# Schematic.net
KiCad netlist of a schematic drawn in Altium Designer
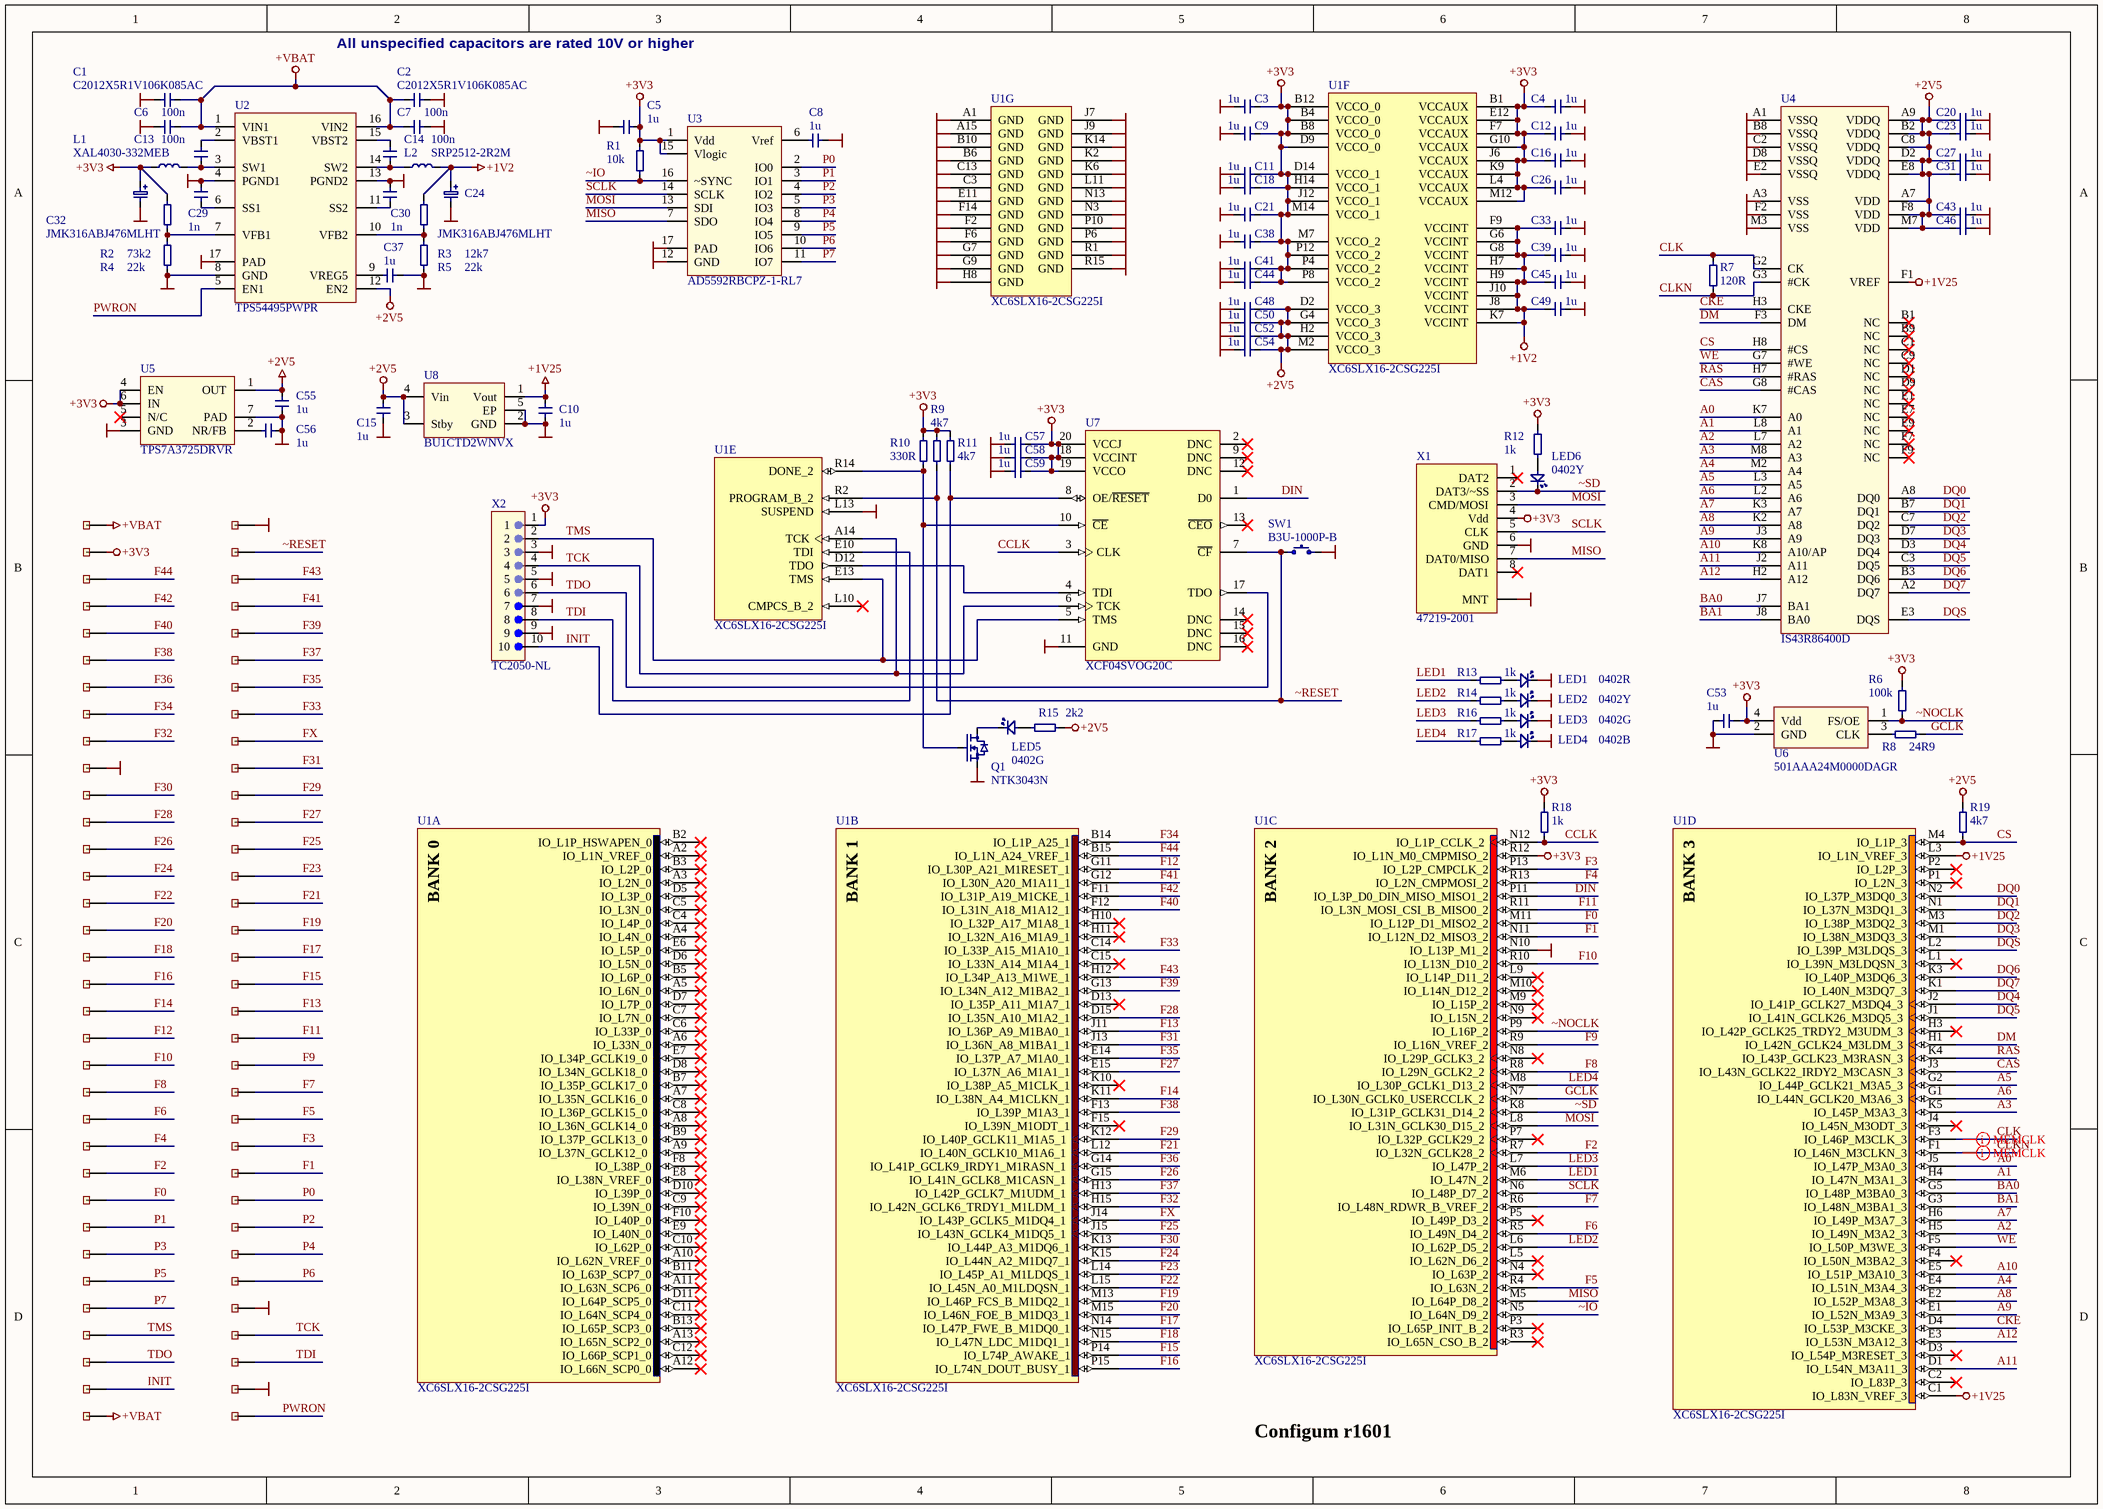
[diagram p0: Schematic.SchDoc]

(export (version "E")
  (design (tool "Eeschema 10.0.6"))
  (components
    (comp (ref "C1")
      (value "C2012X5R1V106K085AC")
      (footprint "_0805")
      (description "Capacitor")
      (libsource (lib "Discretes") (part "Capacitor"))
    )
    (comp (ref "C2")
      (value "C2012X5R1V106K085AC")
      (footprint "_0805")
      (description "Capacitor")
      (libsource (lib "Discretes") (part "Capacitor"))
    )
    (comp (ref "C3")
      (value "1u")
      (footprint "_0402")
      (description "Capacitor")
      (libsource (lib "Discretes") (part "Capacitor"))
    )
    (comp (ref "C4")
      (value "1u")
      (footprint "_0402")
      (description "Capacitor")
      (libsource (lib "Discretes") (part "Capacitor"))
    )
    (comp (ref "C5")
      (value "1u")
      (footprint "_0402")
      (description "Capacitor")
      (libsource (lib "Discretes") (part "Capacitor"))
    )
    (comp (ref "C6")
      (value "100n")
      (footprint "_0402")
      (description "Capacitor")
      (libsource (lib "Discretes") (part "Capacitor"))
    )
    (comp (ref "C7")
      (value "100n")
      (footprint "_0402")
      (description "Capacitor")
      (libsource (lib "Discretes") (part "Capacitor"))
    )
    (comp (ref "C8")
      (value "1u")
      (footprint "_0402")
      (description "Capacitor")
      (libsource (lib "Discretes") (part "Capacitor"))
    )
    (comp (ref "C9")
      (value "1u")
      (footprint "_0402")
      (description "Capacitor")
      (libsource (lib "Discretes") (part "Capacitor"))
    )
    (comp (ref "C10")
      (value "1u")
      (footprint "_0402")
      (description "Capacitor")
      (libsource (lib "Discretes") (part "Capacitor"))
    )
    (comp (ref "C11")
      (value "1u")
      (footprint "_0402")
      (description "Capacitor")
      (libsource (lib "Discretes") (part "Capacitor"))
    )
    (comp (ref "C12")
      (value "1u")
      (footprint "_0402")
      (description "Capacitor")
      (libsource (lib "Discretes") (part "Capacitor"))
    )
    (comp (ref "C13")
      (value "100n")
      (footprint "_0402")
      (description "Capacitor")
      (libsource (lib "Discretes") (part "Capacitor"))
    )
    (comp (ref "C14")
      (value "100n")
      (footprint "_0402")
      (description "Capacitor")
      (libsource (lib "Discretes") (part "Capacitor"))
    )
    (comp (ref "C15")
      (value "1u")
      (footprint "_0402")
      (description "Capacitor")
      (libsource (lib "Discretes") (part "Capacitor"))
    )
    (comp (ref "C16")
      (value "1u")
      (footprint "_0402")
      (description "Capacitor")
      (libsource (lib "Discretes") (part "Capacitor"))
    )
    (comp (ref "C18")
      (value "1u")
      (footprint "_0402")
      (description "Capacitor")
      (libsource (lib "Discretes") (part "Capacitor"))
    )
    (comp (ref "C20")
      (value "1u")
      (footprint "_0402")
      (description "Capacitor")
      (libsource (lib "Discretes") (part "Capacitor"))
    )
    (comp (ref "C21")
      (value "1u")
      (footprint "_0402")
      (description "Capacitor")
      (libsource (lib "Discretes") (part "Capacitor"))
    )
    (comp (ref "C23")
      (value "1u")
      (footprint "_0402")
      (description "Capacitor")
      (libsource (lib "Discretes") (part "Capacitor"))
    )
    (comp (ref "C24")
      (value "JMK316ABJ476MLHT")
      (footprint "Case A (3216)")
      (description "Polar capacitor")
      (libsource (lib "Discretes") (part "Capacitor+"))
    )
    (comp (ref "C26")
      (value "1u")
      (footprint "_0402")
      (description "Capacitor")
      (libsource (lib "Discretes") (part "Capacitor"))
    )
    (comp (ref "C27")
      (value "1u")
      (footprint "_0402")
      (description "Capacitor")
      (libsource (lib "Discretes") (part "Capacitor"))
    )
    (comp (ref "C29")
      (value "1n")
      (footprint "_0402")
      (description "Capacitor")
      (libsource (lib "Discretes") (part "Capacitor"))
    )
    (comp (ref "C30")
      (value "1n")
      (footprint "_0402")
      (description "Capacitor")
      (libsource (lib "Discretes") (part "Capacitor"))
    )
    (comp (ref "C31")
      (value "1u")
      (footprint "_0402")
      (description "Capacitor")
      (libsource (lib "Discretes") (part "Capacitor"))
    )
    (comp (ref "C32")
      (value "JMK316ABJ476MLHT")
      (footprint "Case A (3216)")
      (description "Polar capacitor")
      (libsource (lib "Discretes") (part "Capacitor+"))
    )
    (comp (ref "C33")
      (value "1u")
      (footprint "_0402")
      (description "Capacitor")
      (libsource (lib "Discretes") (part "Capacitor"))
    )
    (comp (ref "C37")
      (value "1u")
      (footprint "_0402")
      (description "Capacitor")
      (libsource (lib "Discretes") (part "Capacitor"))
    )
    (comp (ref "C38")
      (value "1u")
      (footprint "_0402")
      (description "Capacitor")
      (libsource (lib "Discretes") (part "Capacitor"))
    )
    (comp (ref "C39")
      (value "1u")
      (footprint "_0402")
      (description "Capacitor")
      (libsource (lib "Discretes") (part "Capacitor"))
    )
    (comp (ref "C41")
      (value "1u")
      (footprint "_0402")
      (description "Capacitor")
      (libsource (lib "Discretes") (part "Capacitor"))
    )
    (comp (ref "C43")
      (value "1u")
      (footprint "_0402")
      (description "Capacitor")
      (libsource (lib "Discretes") (part "Capacitor"))
    )
    (comp (ref "C44")
      (value "1u")
      (footprint "_0402")
      (description "Capacitor")
      (libsource (lib "Discretes") (part "Capacitor"))
    )
    (comp (ref "C45")
      (value "1u")
      (footprint "_0402")
      (description "Capacitor")
      (libsource (lib "Discretes") (part "Capacitor"))
    )
    (comp (ref "C46")
      (value "1u")
      (footprint "_0402")
      (description "Capacitor")
      (libsource (lib "Discretes") (part "Capacitor"))
    )
    (comp (ref "C48")
      (value "1u")
      (footprint "_0402")
      (description "Capacitor")
      (libsource (lib "Discretes") (part "Capacitor"))
    )
    (comp (ref "C49")
      (value "1u")
      (footprint "_0402")
      (description "Capacitor")
      (libsource (lib "Discretes") (part "Capacitor"))
    )
    (comp (ref "C50")
      (value "1u")
      (footprint "_0402")
      (description "Capacitor")
      (libsource (lib "Discretes") (part "Capacitor"))
    )
    (comp (ref "C52")
      (value "1u")
      (footprint "_0402")
      (description "Capacitor")
      (libsource (lib "Discretes") (part "Capacitor"))
    )
    (comp (ref "C53")
      (value "1u")
      (footprint "_0402")
      (description "Capacitor")
      (libsource (lib "Discretes") (part "Capacitor"))
    )
    (comp (ref "C54")
      (value "1u")
      (footprint "_0402")
      (description "Capacitor")
      (libsource (lib "Discretes") (part "Capacitor"))
    )
    (comp (ref "C55")
      (value "1u")
      (footprint "_0402")
      (description "Capacitor")
      (libsource (lib "Discretes") (part "Capacitor"))
    )
    (comp (ref "C56")
      (value "1u")
      (footprint "_0402")
      (description "Capacitor")
      (libsource (lib "Discretes") (part "Capacitor"))
    )
    (comp (ref "C57")
      (value "1u")
      (footprint "_0402")
      (description "Capacitor")
      (libsource (lib "Discretes") (part "Capacitor"))
    )
    (comp (ref "C58")
      (value "1u")
      (footprint "_0402")
      (description "Capacitor")
      (libsource (lib "Discretes") (part "Capacitor"))
    )
    (comp (ref "C59")
      (value "1u")
      (footprint "_0402")
      (description "Capacitor")
      (libsource (lib "Discretes") (part "Capacitor"))
    )
    (comp (ref "L1")
      (value "XAL4030-332MEB")
      (footprint "IND_4X4")
      (description "Inductor")
      (libsource (lib "Discretes") (part "Inductor"))
    )
    (comp (ref "L2")
      (value "SRP2512-2R2M")
      (footprint "IND_2.5x2")
      (description "Inductor")
      (libsource (lib "") (part "Inductor_1"))
    )
    (comp (ref "LED1")
      (value "0402R")
      (footprint "_0402+")
      (description "Light Emitting Diode")
      (libsource (lib "") (part "LED_1"))
    )
    (comp (ref "LED2")
      (value "0402Y")
      (footprint "_0402+")
      (description "Light Emitting Diode")
      (libsource (lib "") (part "LED_1"))
    )
    (comp (ref "LED3")
      (value "0402G")
      (footprint "_0402+")
      (description "Light Emitting Diode")
      (libsource (lib "") (part "LED_1"))
    )
    (comp (ref "LED4")
      (value "0402B")
      (footprint "_0402+")
      (description "Light Emitting Diode")
      (libsource (lib "") (part "LED_1"))
    )
    (comp (ref "LED5")
      (value "0402G")
      (footprint "_0402+")
      (description "Light Emitting Diode")
      (libsource (lib "Discretes") (part "LED"))
    )
    (comp (ref "LED6")
      (value "0402Y")
      (footprint "_0402+")
      (description "Light Emitting Diode")
      (libsource (lib "Discretes") (part "LED"))
    )
    (comp (ref "PIN1")
      (value "Pin/Pad")
      (footprint "PLCC68 pin")
      (description "Single pin/pad")
      (libsource (lib "") (part "Pin/Pad_56"))
    )
    (comp (ref "PIN2")
      (value "Pin/Pad")
      (footprint "PLCC68 pin")
      (description "Single pin/pad")
      (libsource (lib "") (part "Pin/Pad_62"))
    )
    (comp (ref "PIN3")
      (value "Pin/Pad")
      (footprint "PLCC68 pin")
      (description "Single pin/pad")
      (libsource (lib "") (part "Pin/Pad_10"))
    )
    (comp (ref "PIN4")
      (value "Pin/Pad")
      (footprint "PLCC68 pin")
      (description "Single pin/pad")
      (libsource (lib "") (part "Pin/Pad_3"))
    )
    (comp (ref "PIN5")
      (value "Pin/Pad")
      (footprint "PLCC68 pin")
      (description "Single pin/pad")
      (libsource (lib "") (part "Pin/Pad_43"))
    )
    (comp (ref "PIN6")
      (value "Pin/Pad")
      (footprint "PLCC68 pin")
      (description "Single pin/pad")
      (libsource (lib "") (part "Pin/Pad_8"))
    )
    (comp (ref "PIN7")
      (value "Pin/Pad")
      (footprint "PLCC68 pin")
      (description "Single pin/pad")
      (libsource (lib "Connectors") (part "Pin/Pad"))
    )
    (comp (ref "PIN8")
      (value "Pin/Pad")
      (footprint "PLCC68 pin")
      (description "Single pin/pad")
      (libsource (lib "") (part "Pin/Pad_17"))
    )
    (comp (ref "PIN9")
      (value "Pin/Pad")
      (footprint "PLCC68 pin")
      (description "Single pin/pad")
      (libsource (lib "") (part "Pin/Pad_23"))
    )
    (comp (ref "PIN10")
      (value "Pin/Pad")
      (footprint "PLCC68 pin")
      (description "Single pin/pad")
      (libsource (lib "") (part "Pin/Pad_14"))
    )
    (comp (ref "PIN11")
      (value "Pin/Pad")
      (footprint "PLCC68 pin")
      (description "Single pin/pad")
      (libsource (lib "") (part "Pin/Pad_6"))
    )
    (comp (ref "PIN12")
      (value "Pin/Pad")
      (footprint "PLCC68 pin")
      (description "Single pin/pad")
      (libsource (lib "") (part "Pin/Pad_39"))
    )
    (comp (ref "PIN13")
      (value "Pin/Pad")
      (footprint "PLCC68 pin")
      (description "Single pin/pad")
      (libsource (lib "") (part "Pin/Pad_1"))
    )
    (comp (ref "PIN14")
      (value "Pin/Pad")
      (footprint "PLCC68 pin")
      (description "Single pin/pad")
      (libsource (lib "") (part "Pin/Pad_25"))
    )
    (comp (ref "PIN15")
      (value "Pin/Pad")
      (footprint "PLCC68 pin")
      (description "Single pin/pad")
      (libsource (lib "") (part "Pin/Pad_61"))
    )
    (comp (ref "PIN16")
      (value "Pin/Pad")
      (footprint "PLCC68 pin")
      (description "Single pin/pad")
      (libsource (lib "") (part "Pin/Pad_4"))
    )
    (comp (ref "PIN17")
      (value "Pin/Pad")
      (footprint "PLCC68 pin")
      (description "Single pin/pad")
      (libsource (lib "") (part "Pin/Pad_11"))
    )
    (comp (ref "PIN18")
      (value "Pin/Pad")
      (footprint "PLCC68 pin")
      (description "Single pin/pad")
      (libsource (lib "") (part "Pin/Pad_67"))
    )
    (comp (ref "PIN19")
      (value "Pin/Pad")
      (footprint "PLCC68 pin")
      (description "Single pin/pad")
      (libsource (lib "") (part "Pin/Pad_28"))
    )
    (comp (ref "PIN20")
      (value "Pin/Pad")
      (footprint "PLCC68 pin")
      (description "Single pin/pad")
      (libsource (lib "") (part "Pin/Pad_59"))
    )
    (comp (ref "PIN21")
      (value "Pin/Pad")
      (footprint "PLCC68 pin")
      (description "Single pin/pad")
      (libsource (lib "") (part "Pin/Pad_55"))
    )
    (comp (ref "PIN22")
      (value "Pin/Pad")
      (footprint "PLCC68 pin")
      (description "Single pin/pad")
      (libsource (lib "") (part "Pin/Pad_5"))
    )
    (comp (ref "PIN23")
      (value "Pin/Pad")
      (footprint "PLCC68 pin")
      (description "Single pin/pad")
      (libsource (lib "") (part "Pin/Pad_53"))
    )
    (comp (ref "PIN24")
      (value "Pin/Pad")
      (footprint "PLCC68 pin")
      (description "Single pin/pad")
      (libsource (lib "") (part "Pin/Pad_13"))
    )
    (comp (ref "PIN25")
      (value "Pin/Pad")
      (footprint "PLCC68 pin")
      (description "Single pin/pad")
      (libsource (lib "") (part "Pin/Pad_42"))
    )
    (comp (ref "PIN26")
      (value "Pin/Pad")
      (footprint "PLCC68 pin")
      (description "Single pin/pad")
      (libsource (lib "") (part "Pin/Pad_15"))
    )
    (comp (ref "PIN27")
      (value "Pin/Pad")
      (footprint "PLCC68 pin")
      (description "Single pin/pad")
      (libsource (lib "") (part "Pin/Pad_54"))
    )
    (comp (ref "PIN28")
      (value "Pin/Pad")
      (footprint "PLCC68 pin")
      (description "Single pin/pad")
      (libsource (lib "") (part "Pin/Pad_2"))
    )
    (comp (ref "PIN29")
      (value "Pin/Pad")
      (footprint "PLCC68 pin")
      (description "Single pin/pad")
      (libsource (lib "") (part "Pin/Pad_63"))
    )
    (comp (ref "PIN30")
      (value "Pin/Pad")
      (footprint "PLCC68 pin")
      (description "Single pin/pad")
      (libsource (lib "") (part "Pin/Pad_36"))
    )
    (comp (ref "PIN31")
      (value "Pin/Pad")
      (footprint "PLCC68 pin")
      (description "Single pin/pad")
      (libsource (lib "") (part "Pin/Pad_45"))
    )
    (comp (ref "PIN32")
      (value "Pin/Pad")
      (footprint "PLCC68 pin")
      (description "Single pin/pad")
      (libsource (lib "") (part "Pin/Pad_46"))
    )
    (comp (ref "PIN33")
      (value "Pin/Pad")
      (footprint "PLCC68 pin")
      (description "Single pin/pad")
      (libsource (lib "") (part "Pin/Pad_18"))
    )
    (comp (ref "PIN34")
      (value "Pin/Pad")
      (footprint "PLCC68 pin")
      (description "Single pin/pad")
      (libsource (lib "") (part "Pin/Pad_50"))
    )
    (comp (ref "PIN35")
      (value "Pin/Pad")
      (footprint "PLCC68 pin")
      (description "Single pin/pad")
      (libsource (lib "") (part "Pin/Pad_65"))
    )
    (comp (ref "PIN36")
      (value "Pin/Pad")
      (footprint "PLCC68 pin")
      (description "Single pin/pad")
      (libsource (lib "") (part "Pin/Pad_35"))
    )
    (comp (ref "PIN37")
      (value "Pin/Pad")
      (footprint "PLCC68 pin")
      (description "Single pin/pad")
      (libsource (lib "") (part "Pin/Pad_31"))
    )
    (comp (ref "PIN38")
      (value "Pin/Pad")
      (footprint "PLCC68 pin")
      (description "Single pin/pad")
      (libsource (lib "") (part "Pin/Pad_66"))
    )
    (comp (ref "PIN39")
      (value "Pin/Pad")
      (footprint "PLCC68 pin")
      (description "Single pin/pad")
      (libsource (lib "") (part "Pin/Pad_9"))
    )
    (comp (ref "PIN40")
      (value "Pin/Pad")
      (footprint "PLCC68 pin")
      (description "Single pin/pad")
      (libsource (lib "") (part "Pin/Pad_58"))
    )
    (comp (ref "PIN41")
      (value "Pin/Pad")
      (footprint "PLCC68 pin")
      (description "Single pin/pad")
      (libsource (lib "") (part "Pin/Pad_26"))
    )
    (comp (ref "PIN42")
      (value "Pin/Pad")
      (footprint "PLCC68 pin")
      (description "Single pin/pad")
      (libsource (lib "") (part "Pin/Pad_12"))
    )
    (comp (ref "PIN43")
      (value "Pin/Pad")
      (footprint "PLCC68 pin")
      (description "Single pin/pad")
      (libsource (lib "") (part "Pin/Pad_49"))
    )
    (comp (ref "PIN44")
      (value "Pin/Pad")
      (footprint "PLCC68 pin")
      (description "Single pin/pad")
      (libsource (lib "") (part "Pin/Pad_21"))
    )
    (comp (ref "PIN45")
      (value "Pin/Pad")
      (footprint "PLCC68 pin")
      (description "Single pin/pad")
      (libsource (lib "") (part "Pin/Pad_33"))
    )
    (comp (ref "PIN46")
      (value "Pin/Pad")
      (footprint "PLCC68 pin")
      (description "Single pin/pad")
      (libsource (lib "") (part "Pin/Pad_20"))
    )
    (comp (ref "PIN47")
      (value "Pin/Pad")
      (footprint "PLCC68 pin")
      (description "Single pin/pad")
      (libsource (lib "") (part "Pin/Pad_16"))
    )
    (comp (ref "PIN48")
      (value "Pin/Pad")
      (footprint "PLCC68 pin")
      (description "Single pin/pad")
      (libsource (lib "") (part "Pin/Pad_22"))
    )
    (comp (ref "PIN49")
      (value "Pin/Pad")
      (footprint "PLCC68 pin")
      (description "Single pin/pad")
      (libsource (lib "") (part "Pin/Pad_32"))
    )
    (comp (ref "PIN50")
      (value "Pin/Pad")
      (footprint "PLCC68 pin")
      (description "Single pin/pad")
      (libsource (lib "") (part "Pin/Pad_41"))
    )
    (comp (ref "PIN51")
      (value "Pin/Pad")
      (footprint "PLCC68 pin")
      (description "Single pin/pad")
      (libsource (lib "") (part "Pin/Pad_37"))
    )
    (comp (ref "PIN52")
      (value "Pin/Pad")
      (footprint "PLCC68 pin")
      (description "Single pin/pad")
      (libsource (lib "") (part "Pin/Pad_47"))
    )
    (comp (ref "PIN53")
      (value "Pin/Pad")
      (footprint "PLCC68 pin")
      (description "Single pin/pad")
      (libsource (lib "") (part "Pin/Pad_19"))
    )
    (comp (ref "PIN54")
      (value "Pin/Pad")
      (footprint "PLCC68 pin")
      (description "Single pin/pad")
      (libsource (lib "") (part "Pin/Pad_60"))
    )
    (comp (ref "PIN55")
      (value "Pin/Pad")
      (footprint "PLCC68 pin")
      (description "Single pin/pad")
      (libsource (lib "") (part "Pin/Pad_51"))
    )
    (comp (ref "PIN56")
      (value "Pin/Pad")
      (footprint "PLCC68 pin")
      (description "Single pin/pad")
      (libsource (lib "") (part "Pin/Pad_29"))
    )
    (comp (ref "PIN57")
      (value "Pin/Pad")
      (footprint "PLCC68 pin")
      (description "Single pin/pad")
      (libsource (lib "") (part "Pin/Pad_57"))
    )
    (comp (ref "PIN58")
      (value "Pin/Pad")
      (footprint "PLCC68 pin")
      (description "Single pin/pad")
      (libsource (lib "") (part "Pin/Pad_48"))
    )
    (comp (ref "PIN59")
      (value "Pin/Pad")
      (footprint "PLCC68 pin")
      (description "Single pin/pad")
      (libsource (lib "") (part "Pin/Pad_38"))
    )
    (comp (ref "PIN60")
      (value "Pin/Pad")
      (footprint "PLCC68 pin")
      (description "Single pin/pad")
      (libsource (lib "") (part "Pin/Pad_24"))
    )
    (comp (ref "PIN61")
      (value "Pin/Pad")
      (footprint "PLCC68 pin")
      (description "Single pin/pad")
      (libsource (lib "") (part "Pin/Pad_44"))
    )
    (comp (ref "PIN62")
      (value "Pin/Pad")
      (footprint "PLCC68 pin")
      (description "Single pin/pad")
      (libsource (lib "") (part "Pin/Pad_52"))
    )
    (comp (ref "PIN63")
      (value "Pin/Pad")
      (footprint "PLCC68 pin")
      (description "Single pin/pad")
      (libsource (lib "") (part "Pin/Pad_40"))
    )
    (comp (ref "PIN64")
      (value "Pin/Pad")
      (footprint "PLCC68 pin")
      (description "Single pin/pad")
      (libsource (lib "") (part "Pin/Pad_7"))
    )
    (comp (ref "PIN65")
      (value "Pin/Pad")
      (footprint "PLCC68 pin")
      (description "Single pin/pad")
      (libsource (lib "") (part "Pin/Pad_34"))
    )
    (comp (ref "PIN66")
      (value "Pin/Pad")
      (footprint "PLCC68 pin")
      (description "Single pin/pad")
      (libsource (lib "") (part "Pin/Pad_64"))
    )
    (comp (ref "PIN67")
      (value "Pin/Pad")
      (footprint "PLCC68 pin")
      (description "Single pin/pad")
      (libsource (lib "") (part "Pin/Pad_30"))
    )
    (comp (ref "PIN68")
      (value "Pin/Pad")
      (footprint "PLCC68 pin")
      (description "Single pin/pad")
      (libsource (lib "") (part "Pin/Pad_27"))
    )
    (comp (ref "Q1")
      (value "NTK3043N")
      (footprint "SC105-3")
      (description "N-channel FET transistor")
      (libsource (lib "Discretes") (part "N-FET"))
    )
    (comp (ref "R1")
      (value "10k")
      (footprint "_0402")
      (description "Resistor")
      (libsource (lib "") (part "Resistor_2"))
    )
    (comp (ref "R2")
      (value "73k2")
      (footprint "_0402")
      (description "Resistor")
      (libsource (lib "Discretes") (part "Resistor"))
    )
    (comp (ref "R3")
      (value "12k7")
      (footprint "_0402")
      (description "Resistor")
      (libsource (lib "Discretes") (part "Resistor"))
    )
    (comp (ref "R4")
      (value "22k")
      (footprint "_0402")
      (description "Resistor")
      (libsource (lib "Discretes") (part "Resistor"))
    )
    (comp (ref "R5")
      (value "22k")
      (footprint "_0402")
      (description "Resistor")
      (libsource (lib "Discretes") (part "Resistor"))
    )
    (comp (ref "R6")
      (value "100k")
      (footprint "_0402")
      (description "Resistor")
      (libsource (lib "") (part "Resistor_2"))
    )
    (comp (ref "R7")
      (value "120R")
      (footprint "_0402")
      (description "Resistor")
      (libsource (lib "") (part "Resistor_2"))
    )
    (comp (ref "R8")
      (value "24R9")
      (footprint "_0402")
      (description "Resistor")
      (libsource (lib "") (part "Resistor_3"))
    )
    (comp (ref "R9")
      (value "4k7")
      (footprint "_0402")
      (description "Resistor")
      (libsource (lib "") (part "Resistor_2"))
    )
    (comp (ref "R10")
      (value "330R")
      (footprint "_0402")
      (description "Resistor")
      (libsource (lib "") (part "Resistor_2"))
    )
    (comp (ref "R11")
      (value "4k7")
      (footprint "_0402")
      (description "Resistor")
      (libsource (lib "") (part "Resistor_2"))
    )
    (comp (ref "R12")
      (value "1k")
      (footprint "_0402")
      (description "Resistor")
      (libsource (lib "") (part "Resistor_2"))
    )
    (comp (ref "R13")
      (value "1k")
      (footprint "_0402")
      (description "Resistor")
      (libsource (lib "") (part "Resistor_1"))
    )
    (comp (ref "R14")
      (value "1k")
      (footprint "_0402")
      (description "Resistor")
      (libsource (lib "") (part "Resistor_1"))
    )
    (comp (ref "R15")
      (value "2k2")
      (footprint "_0402")
      (description "Resistor")
      (libsource (lib "") (part "Resistor_3"))
    )
    (comp (ref "R16")
      (value "1k")
      (footprint "_0402")
      (description "Resistor")
      (libsource (lib "") (part "Resistor_1"))
    )
    (comp (ref "R17")
      (value "1k")
      (footprint "_0402")
      (description "Resistor")
      (libsource (lib "") (part "Resistor_1"))
    )
    (comp (ref "R18")
      (value "1k")
      (footprint "_0402")
      (description "Resistor")
      (libsource (lib "Discretes") (part "Resistor"))
    )
    (comp (ref "R19")
      (value "4k7")
      (footprint "_0402")
      (description "Resistor")
      (libsource (lib "Discretes") (part "Resistor"))
    )
    (comp (ref "SW1")
      (value "B3U-1000P-B")
      (footprint "B3U-1000P-B")
      (description "Switch, Momentary, Normal Open, SPST")
      (libsource (lib "Switches") (part "Switch MNO SPST"))
    )
    (comp (ref "U1")
      (value "XC6SLX16-2CSG225I")
      (footprint "CSG225")
      (libsource (lib "Xilinx Spartan-6") (part "XC6SLX16-2CSG225I"))
    )
    (comp (ref "U2")
      (value "TPS54495PWPR")
      (footprint "TSOP65P650X110_HS-16N")
      (description "4A/2A Dual Channel Synchronous Step-Down Switcher with Integrated FET")
      (fields (field (name "MANUFACTURER") "Texas Instruments"))
      (libsource (lib "IC Power Supply") (part "TPS54495 TSSOP16"))
    )
    (comp (ref "U3")
      (value "AD5592RBCPZ-1-RL7")
      (footprint "QFN50P300X300-16V4N")
      (description "8-Channel, 12-Bit, Configurable ADC/DAC with On-Chip Reference, SPI Interface")
      (fields (field (name "MANUFACTURER") "Analog Devices"))
      (libsource (lib "IC Other Functions") (part "AD5592R-1 QFN16"))
    )
    (comp (ref "U4")
      (value "IS43R86400D")
      (footprint "BGA60C80P12X9_1300X800X120")
      (description "64Mx8 DDR SDRAM")
      (fields (field (name "MANUFACTURER") "ISSI"))
      (libsource (lib "IC Other Functions") (part "IS43R86400D FBGA60"))
    )
    (comp (ref "U5")
      (value "TPS7A3725DRVR")
      (footprint "SON65P200x200_HS-6N")
      (description "1% High-Accuracy, 1-A, Low-Dropout Regulator  with Reverse Current Protection")
      (fields (field (name "MANUFACTURER") "Texas Instruments"))
      (libsource (lib "IC Power Supply") (part "TPS7A37"))
    )
    (comp (ref "U6")
      (value "501AAA24M0000DAGR")
      (footprint "Osc 25x20 (4)")
      (description "32kHz –100MHz CMEMS Oscillator")
      (fields (field (name "MANUFACTURER") "Silicon Labs"))
      (libsource (lib "IC Other Functions") (part "Si50x"))
    )
    (comp (ref "U7")
      (value "XCF04SVOG20C")
      (footprint "VOG20_L")
      (libsource (lib "Xilinx XCF") (part "XCF04SVOG20C"))
    )
    (comp (ref "U8")
      (value "BU1CTD2WNVX")
      (footprint "DFN65P100x100-4")
      (description "1.25V 200mA LDO in 1mm x 1mm package")
      (fields (field (name "MANUFACTURER") "Rohm"))
      (libsource (lib "IC Power Supply") (part "BUxxTD2WNVX"))
    )
    (comp (ref "X1")
      (value "47219-2001")
      (footprint "MOLEX_47219-2001")
      (description "microSD card connector")
      (libsource (lib "Connectors") (part "microSD"))
    )
    (comp (ref "X2")
      (value "TC2050-NL")
      (footprint "TC2050-NL")
      (description "TC2050 nails connector")
      (fields (field (name "MANUFACTURER") "www.tag-connect.com"))
      (libsource (lib "Connectors") (part "TC2050"))
    )
  )
  (nets
    (net (code "1") (name "+1V2") (class "Default")
      (node (ref "C24") (pin "1") (pintype "passive"))
      (node (ref "C33") (pin "1") (pintype "passive"))
      (node (ref "C39") (pin "1") (pintype "passive"))
      (node (ref "C45") (pin "1") (pintype "passive"))
      (node (ref "C49") (pin "1") (pintype "passive"))
      (node (ref "L2") (pin "1") (pintype "passive"))
      (node (ref "R3") (pin "2") (pintype "passive"))
      (node (ref "U1") (pin "F9") (pinfunction "VCCINT_F9") (pintype "power_in"))
      (node (ref "U1") (pin "G6") (pinfunction "VCCINT_G6") (pintype "power_in"))
      (node (ref "U1") (pin "G8") (pinfunction "VCCINT_G8") (pintype "power_in"))
      (node (ref "U1") (pin "H7") (pinfunction "VCCINT_H7") (pintype "power_in"))
      (node (ref "U1") (pin "H9") (pinfunction "VCCINT_H9") (pintype "power_in"))
      (node (ref "U1") (pin "J10") (pinfunction "VCCINT_J10") (pintype "power_in"))
      (node (ref "U1") (pin "J8") (pinfunction "VCCINT_J8") (pintype "power_in"))
      (node (ref "U1") (pin "K7") (pinfunction "VCCINT_K7") (pintype "power_in"))
    )
    (net (code "2") (name "+1V25") (class "Default")
      (node (ref "C10") (pin "2") (pintype "passive"))
      (node (ref "U1") (pin "C1") (pinfunction "IO_L83N_VREF_3_C1") (pintype "bidirectional"))
      (node (ref "U1") (pin "L3") (pinfunction "IO_L1N_VREF_3_L3") (pintype "bidirectional"))
      (node (ref "U4") (pin "F1") (pinfunction "VREF_F1") (pintype "passive"))
      (node (ref "U8") (pin "1") (pinfunction "Vout_1") (pintype "passive"))
    )
    (net (code "3") (name "+2V5") (class "Default")
      (node (ref "C15") (pin "2") (pintype "passive"))
      (node (ref "C20") (pin "1") (pintype "passive"))
      (node (ref "C23") (pin "1") (pintype "passive"))
      (node (ref "C27") (pin "1") (pintype "passive"))
      (node (ref "C31") (pin "1") (pintype "passive"))
      (node (ref "C43") (pin "1") (pintype "passive"))
      (node (ref "C46") (pin "1") (pintype "passive"))
      (node (ref "C48") (pin "2") (pintype "passive"))
      (node (ref "C50") (pin "2") (pintype "passive"))
      (node (ref "C52") (pin "2") (pintype "passive"))
      (node (ref "C54") (pin "2") (pintype "passive"))
      (node (ref "C55") (pin "1") (pintype "passive"))
      (node (ref "R15") (pin "2") (pintype "passive"))
      (node (ref "R19") (pin "2") (pintype "passive"))
      (node (ref "U1") (pin "D2") (pinfunction "VCCO_3_D2") (pintype "power_in"))
      (node (ref "U1") (pin "G4") (pinfunction "VCCO_3_G4") (pintype "power_in"))
      (node (ref "U1") (pin "H2") (pinfunction "VCCO_3_H2") (pintype "power_in"))
      (node (ref "U1") (pin "M2") (pinfunction "VCCO_3_M2") (pintype "power_in"))
      (node (ref "U2") (pin "12") (pinfunction "EN2_12") (pintype "passive"))
      (node (ref "U4") (pin "A7") (pinfunction "VDD_A7") (pintype "passive"))
      (node (ref "U4") (pin "A9") (pinfunction "VDDQ_A9") (pintype "passive"))
      (node (ref "U4") (pin "B2") (pinfunction "VDDQ_B2") (pintype "passive"))
      (node (ref "U4") (pin "C8") (pinfunction "VDDQ_C8") (pintype "passive"))
      (node (ref "U4") (pin "D2") (pinfunction "VDDQ_D2") (pintype "passive"))
      (node (ref "U4") (pin "E8") (pinfunction "VDDQ_E8") (pintype "passive"))
      (node (ref "U4") (pin "F8") (pinfunction "VDD_F8") (pintype "passive"))
      (node (ref "U4") (pin "M7") (pinfunction "VDD_M7") (pintype "passive"))
      (node (ref "U5") (pin "1") (pinfunction "OUT_1") (pintype "passive"))
      (node (ref "U8") (pin "3") (pinfunction "Stby_3") (pintype "passive"))
      (node (ref "U8") (pin "4") (pinfunction "Vin_4") (pintype "passive"))
    )
    (net (code "4") (name "+3V3") (class "Default")
      (node (ref "C11") (pin "2") (pintype "passive"))
      (node (ref "C12") (pin "1") (pintype "passive"))
      (node (ref "C16") (pin "1") (pintype "passive"))
      (node (ref "C18") (pin "2") (pintype "passive"))
      (node (ref "C21") (pin "2") (pintype "passive"))
      (node (ref "C26") (pin "1") (pintype "passive"))
      (node (ref "C3") (pin "2") (pintype "passive"))
      (node (ref "C32") (pin "1") (pintype "passive"))
      (node (ref "C38") (pin "2") (pintype "passive"))
      (node (ref "C4") (pin "1") (pintype "passive"))
      (node (ref "C41") (pin "2") (pintype "passive"))
      (node (ref "C44") (pin "2") (pintype "passive"))
      (node (ref "C5") (pin "2") (pintype "passive"))
      (node (ref "C53") (pin "1") (pintype "passive"))
      (node (ref "C57") (pin "2") (pintype "passive"))
      (node (ref "C58") (pin "2") (pintype "passive"))
      (node (ref "C59") (pin "2") (pintype "passive"))
      (node (ref "C9") (pin "2") (pintype "passive"))
      (node (ref "L1") (pin "1") (pintype "passive"))
      (node (ref "PIN3") (pin "12") (pintype "passive"))
      (node (ref "R1") (pin "1") (pintype "passive"))
      (node (ref "R10") (pin "1") (pintype "passive"))
      (node (ref "R11") (pin "1") (pintype "passive"))
      (node (ref "R12") (pin "1") (pintype "passive"))
      (node (ref "R18") (pin "2") (pintype "passive"))
      (node (ref "R2") (pin "2") (pintype "passive"))
      (node (ref "R6") (pin "1") (pintype "passive"))
      (node (ref "R9") (pin "1") (pintype "passive"))
      (node (ref "U1") (pin "B1") (pinfunction "VCCAUX_B1") (pintype "power_in"))
      (node (ref "U1") (pin "B12") (pinfunction "VCCO_0_B12") (pintype "power_in"))
      (node (ref "U1") (pin "B4") (pinfunction "VCCO_0_B4") (pintype "power_in"))
      (node (ref "U1") (pin "B8") (pinfunction "VCCO_0_B8") (pintype "power_in"))
      (node (ref "U1") (pin "D14") (pinfunction "VCCO_1_D14") (pintype "power_in"))
      (node (ref "U1") (pin "D9") (pinfunction "VCCO_0_D9") (pintype "power_in"))
      (node (ref "U1") (pin "E12") (pinfunction "VCCAUX_E12") (pintype "power_in"))
      (node (ref "U1") (pin "F7") (pinfunction "VCCAUX_F7") (pintype "power_in"))
      (node (ref "U1") (pin "G10") (pinfunction "VCCAUX_G10") (pintype "power_in"))
      (node (ref "U1") (pin "H14") (pinfunction "VCCO_1_H14") (pintype "power_in"))
      (node (ref "U1") (pin "J12") (pinfunction "VCCO_1_J12") (pintype "power_in"))
      (node (ref "U1") (pin "J6") (pinfunction "VCCAUX_J6") (pintype "power_in"))
      (node (ref "U1") (pin "K9") (pinfunction "VCCAUX_K9") (pintype "power_in"))
      (node (ref "U1") (pin "L4") (pinfunction "VCCAUX_L4") (pintype "power_in"))
      (node (ref "U1") (pin "M12") (pinfunction "VCCAUX_M12") (pintype "power_in"))
      (node (ref "U1") (pin "M14") (pinfunction "VCCO_1_M14") (pintype "power_in"))
      (node (ref "U1") (pin "M7") (pinfunction "VCCO_2_M7") (pintype "power_in"))
      (node (ref "U1") (pin "P12") (pinfunction "VCCO_2_P12") (pintype "power_in"))
      (node (ref "U1") (pin "P4") (pinfunction "VCCO_2_P4") (pintype "power_in"))
      (node (ref "U1") (pin "P8") (pinfunction "VCCO_2_P8") (pintype "power_in"))
      (node (ref "U1") (pin "R12") (pinfunction "IO_L1N_M0_CMPMISO_2_R12") (pintype "bidirectional"))
      (node (ref "U3") (pin "1") (pinfunction "Vdd_1") (pintype "passive"))
      (node (ref "U3") (pin "15") (pinfunction "Vlogic_15") (pintype "passive"))
      (node (ref "U5") (pin "4") (pinfunction "EN_4") (pintype "passive"))
      (node (ref "U5") (pin "6") (pinfunction "IN_6") (pintype "passive"))
      (node (ref "U6") (pin "4") (pinfunction "Vdd_4") (pintype "passive"))
      (node (ref "U7") (pin "18") (pinfunction "VCCINT_18") (pintype "power_in"))
      (node (ref "U7") (pin "19") (pinfunction "VCCO_19") (pintype "power_in"))
      (node (ref "U7") (pin "20") (pinfunction "VCCJ_20") (pintype "power_in"))
      (node (ref "X1") (pin "4") (pinfunction "Vdd_4") (pintype "passive"))
      (node (ref "X2") (pin "1") (pinfunction "1_1") (pintype "passive"))
    )
    (net (code "5") (name "+VBAT") (class "Default")
      (node (ref "C1") (pin "2") (pintype "passive"))
      (node (ref "C2") (pin "1") (pintype "passive"))
      (node (ref "C6") (pin "2") (pintype "passive"))
      (node (ref "C7") (pin "1") (pintype "passive"))
      (node (ref "PIN1") (pin "10") (pintype "passive"))
      (node (ref "PIN67") (pin "8") (pintype "passive"))
      (node (ref "U2") (pin "1") (pinfunction "VIN1_1") (pintype "passive"))
      (node (ref "U2") (pin "16") (pinfunction "VIN2_16") (pintype "passive"))
    )
    (net (code "6") (name "/A0") (class "Default")
      (node (ref "U1") (pin "J5") (pinfunction "IO_L47P_M3A0_3_J5") (pintype "bidirectional"))
      (node (ref "U4") (pin "K7") (pinfunction "A0_K7") (pintype "passive"))
    )
    (net (code "7") (name "/A1") (class "Default")
      (node (ref "U1") (pin "H4") (pinfunction "IO_L47N_M3A1_3_H4") (pintype "bidirectional"))
      (node (ref "U4") (pin "L8") (pinfunction "A1_L8") (pintype "passive"))
    )
    (net (code "8") (name "/A2") (class "Default")
      (node (ref "U1") (pin "H5") (pinfunction "IO_L49N_M3A2_3_H5") (pintype "bidirectional"))
      (node (ref "U4") (pin "L7") (pinfunction "A2_L7") (pintype "passive"))
    )
    (net (code "9") (name "/A3") (class "Default")
      (node (ref "U1") (pin "K5") (pinfunction "IO_L45P_M3A3_3_K5") (pintype "bidirectional"))
      (node (ref "U4") (pin "M8") (pinfunction "A3_M8") (pintype "passive"))
    )
    (net (code "10") (name "/A4") (class "Default")
      (node (ref "U1") (pin "E4") (pinfunction "IO_L51N_M3A4_3_E4") (pintype "bidirectional"))
      (node (ref "U4") (pin "M2") (pinfunction "A4_M2") (pintype "passive"))
    )
    (net (code "11") (name "/A5") (class "Default")
      (node (ref "U1") (pin "G2") (pinfunction "IO_L44P_GCLK21_M3A5_3_G2") (pintype "bidirectional"))
      (node (ref "U4") (pin "L3") (pinfunction "A5_L3") (pintype "passive"))
    )
    (net (code "12") (name "/A6") (class "Default")
      (node (ref "U1") (pin "G1") (pinfunction "IO_L44N_GCLK20_M3A6_3_G1") (pintype "bidirectional"))
      (node (ref "U4") (pin "L2") (pinfunction "A6_L2") (pintype "passive"))
    )
    (net (code "13") (name "/A7") (class "Default")
      (node (ref "U1") (pin "H6") (pinfunction "IO_L49P_M3A7_3_H6") (pintype "bidirectional"))
      (node (ref "U4") (pin "K3") (pinfunction "A7_K3") (pintype "passive"))
    )
    (net (code "14") (name "/A8") (class "Default")
      (node (ref "U1") (pin "E2") (pinfunction "IO_L52P_M3A8_3_E2") (pintype "bidirectional"))
      (node (ref "U4") (pin "K2") (pinfunction "A8_K2") (pintype "passive"))
    )
    (net (code "15") (name "/A9") (class "Default")
      (node (ref "U1") (pin "E1") (pinfunction "IO_L52N_M3A9_3_E1") (pintype "bidirectional"))
      (node (ref "U4") (pin "J3") (pinfunction "A9_J3") (pintype "passive"))
    )
    (net (code "16") (name "/A10") (class "Default")
      (node (ref "U1") (pin "E5") (pinfunction "IO_L51P_M3A10_3_E5") (pintype "bidirectional"))
      (node (ref "U4") (pin "K8") (pinfunction "A10/AP_K8") (pintype "passive"))
    )
    (net (code "17") (name "/A11") (class "Default")
      (node (ref "U1") (pin "D1") (pinfunction "IO_L54N_M3A11_3_D1") (pintype "bidirectional"))
      (node (ref "U4") (pin "J2") (pinfunction "A11_J2") (pintype "passive"))
    )
    (net (code "18") (name "/A12") (class "Default")
      (node (ref "U1") (pin "E3") (pinfunction "IO_L53N_M3A12_3_E3") (pintype "bidirectional"))
      (node (ref "U4") (pin "H2") (pinfunction "A12_H2") (pintype "passive"))
    )
    (net (code "19") (name "/BA0") (class "Default")
      (node (ref "U1") (pin "G5") (pinfunction "IO_L48P_M3BA0_3_G5") (pintype "bidirectional"))
      (node (ref "U4") (pin "J7") (pinfunction "BA1_J7") (pintype "passive"))
    )
    (net (code "20") (name "/BA1") (class "Default")
      (node (ref "U1") (pin "G3") (pinfunction "IO_L48N_M3BA1_3_G3") (pintype "bidirectional"))
      (node (ref "U4") (pin "J8") (pinfunction "BA0_J8") (pintype "passive"))
    )
    (net (code "21") (name "/CAS") (class "Default")
      (node (ref "U1") (pin "J3") (pinfunction "IO_L43N_GCLK22_IRDY2_M3CASN_3_J3") (pintype "bidirectional"))
      (node (ref "U4") (pin "G8") (pinfunction "#CAS_G8") (pintype "passive"))
    )
    (net (code "22") (name "/CCLK") (class "Default")
      (node (ref "R18") (pin "1") (pintype "passive"))
      (node (ref "U1") (pin "N12") (pinfunction "IO_L1P_CCLK_2_N12") (pintype "bidirectional"))
      (node (ref "U7") (pin "3") (pinfunction "CLK_3") (pintype "input"))
    )
    (net (code "23") (name "/CKE") (class "Default")
      (node (ref "U1") (pin "D4") (pinfunction "IO_L53P_M3CKE_3_D4") (pintype "bidirectional"))
      (node (ref "U4") (pin "H3") (pinfunction "CKE_H3") (pintype "passive"))
    )
    (net (code "24") (name "/CLK") (class "Default")
      (node (ref "R7") (pin "1") (pintype "passive"))
      (node (ref "U1") (pin "F3") (pinfunction "IO_L46P_M3CLK_3_F3") (pintype "bidirectional"))
      (node (ref "U4") (pin "G2") (pinfunction "CK_G2") (pintype "passive"))
    )
    (net (code "25") (name "/CLKN") (class "Default")
      (node (ref "R7") (pin "2") (pintype "passive"))
      (node (ref "U1") (pin "F1") (pinfunction "IO_L46N_M3CLKN_3_F1") (pintype "bidirectional"))
      (node (ref "U4") (pin "G3") (pinfunction "#CK_G3") (pintype "passive"))
    )
    (net (code "26") (name "/CS") (class "Default")
      (node (ref "R19") (pin "1") (pintype "passive"))
      (node (ref "U1") (pin "M4") (pinfunction "IO_L1P_3_M4") (pintype "bidirectional"))
      (node (ref "U4") (pin "H8") (pinfunction "#CS_H8") (pintype "passive"))
    )
    (net (code "27") (name "/DIN") (class "Default")
      (node (ref "U1") (pin "P11") (pinfunction "IO_L3P_D0_DIN_MISO_MISO1_2_P11") (pintype "bidirectional"))
      (node (ref "U7") (pin "1") (pinfunction "D0_1") (pintype "tri_state"))
    )
    (net (code "28") (name "/DM") (class "Default")
      (node (ref "U1") (pin "H1") (pinfunction "IO_L42N_GCLK24_M3LDM_3_H1") (pintype "bidirectional"))
      (node (ref "U4") (pin "F3") (pinfunction "DM_F3") (pintype "passive"))
    )
    (net (code "29") (name "/DQ0") (class "Default")
      (node (ref "U1") (pin "N2") (pinfunction "IO_L37P_M3DQ0_3_N2") (pintype "bidirectional"))
      (node (ref "U4") (pin "A8") (pinfunction "DQ0_A8") (pintype "passive"))
    )
    (net (code "30") (name "/DQ1") (class "Default")
      (node (ref "U1") (pin "N1") (pinfunction "IO_L37N_M3DQ1_3_N1") (pintype "bidirectional"))
      (node (ref "U4") (pin "B7") (pinfunction "DQ1_B7") (pintype "passive"))
    )
    (net (code "31") (name "/DQ2") (class "Default")
      (node (ref "U1") (pin "M3") (pinfunction "IO_L38P_M3DQ2_3_M3") (pintype "bidirectional"))
      (node (ref "U4") (pin "C7") (pinfunction "DQ2_C7") (pintype "passive"))
    )
    (net (code "32") (name "/DQ3") (class "Default")
      (node (ref "U1") (pin "M1") (pinfunction "IO_L38N_M3DQ3_3_M1") (pintype "bidirectional"))
      (node (ref "U4") (pin "D7") (pinfunction "DQ3_D7") (pintype "passive"))
    )
    (net (code "33") (name "/DQ4") (class "Default")
      (node (ref "U1") (pin "J2") (pinfunction "IO_L41P_GCLK27_M3DQ4_3_J2") (pintype "bidirectional"))
      (node (ref "U4") (pin "D3") (pinfunction "DQ4_D3") (pintype "passive"))
    )
    (net (code "34") (name "/DQ5") (class "Default")
      (node (ref "U1") (pin "J1") (pinfunction "IO_L41N_GCLK26_M3DQ5_3_J1") (pintype "bidirectional"))
      (node (ref "U4") (pin "C3") (pinfunction "DQ5_C3") (pintype "passive"))
    )
    (net (code "35") (name "/DQ6") (class "Default")
      (node (ref "U1") (pin "K3") (pinfunction "IO_L40P_M3DQ6_3_K3") (pintype "bidirectional"))
      (node (ref "U4") (pin "B3") (pinfunction "DQ6_B3") (pintype "passive"))
    )
    (net (code "36") (name "/DQ7") (class "Default")
      (node (ref "U1") (pin "K1") (pinfunction "IO_L40N_M3DQ7_3_K1") (pintype "bidirectional"))
      (node (ref "U4") (pin "A2") (pinfunction "DQ7_A2") (pintype "passive"))
    )
    (net (code "37") (name "/DQS") (class "Default")
      (node (ref "U1") (pin "L2") (pinfunction "IO_L39P_M3LDQS_3_L2") (pintype "bidirectional"))
      (node (ref "U4") (pin "E3") (pinfunction "DQS_E3") (pintype "passive"))
    )
    (net (code "38") (name "/F0") (class "Default")
      (node (ref "PIN51") (pin "60") (pintype "passive"))
      (node (ref "U1") (pin "M11") (pinfunction "IO_L12P_D1_MISO2_2_M11") (pintype "bidirectional"))
    )
    (net (code "39") (name "/F1") (class "Default")
      (node (ref "PIN50") (pin "59") (pintype "passive"))
      (node (ref "U1") (pin "N11") (pinfunction "IO_L12N_D2_MISO3_2_N11") (pintype "bidirectional"))
    )
    (net (code "40") (name "/F2") (class "Default")
      (node (ref "PIN49") (pin "58") (pintype "passive"))
      (node (ref "U1") (pin "R7") (pinfunction "IO_L32N_GCLK28_2_R7") (pintype "bidirectional"))
    )
    (net (code "41") (name "/F3") (class "Default")
      (node (ref "PIN48") (pin "57") (pintype "passive"))
      (node (ref "U1") (pin "P13") (pinfunction "IO_L2P_CMPCLK_2_P13") (pintype "bidirectional"))
    )
    (net (code "42") (name "/F4") (class "Default")
      (node (ref "PIN47") (pin "56") (pintype "passive"))
      (node (ref "U1") (pin "R13") (pinfunction "IO_L2N_CMPMOSI_2_R13") (pintype "bidirectional"))
    )
    (net (code "43") (name "/F5") (class "Default")
      (node (ref "PIN46") (pin "55") (pintype "passive"))
      (node (ref "U1") (pin "R4") (pinfunction "IO_L63N_2_R4") (pintype "bidirectional"))
    )
    (net (code "44") (name "/F6") (class "Default")
      (node (ref "PIN45") (pin "54") (pintype "passive"))
      (node (ref "U1") (pin "R5") (pinfunction "IO_L49N_D4_2_R5") (pintype "bidirectional"))
    )
    (net (code "45") (name "/F7") (class "Default")
      (node (ref "PIN44") (pin "53") (pintype "passive"))
      (node (ref "U1") (pin "R6") (pinfunction "IO_L48N_RDWR_B_VREF_2_R6") (pintype "bidirectional"))
    )
    (net (code "46") (name "/F8") (class "Default")
      (node (ref "PIN43") (pin "52") (pintype "passive"))
      (node (ref "U1") (pin "R8") (pinfunction "IO_L29N_GCLK2_2_R8") (pintype "bidirectional"))
    )
    (net (code "47") (name "/F9") (class "Default")
      (node (ref "PIN42") (pin "51") (pintype "passive"))
      (node (ref "U1") (pin "R9") (pinfunction "IO_L16N_VREF_2_R9") (pintype "bidirectional"))
    )
    (net (code "48") (name "/F10") (class "Default")
      (node (ref "PIN41") (pin "50") (pintype "passive"))
      (node (ref "U1") (pin "R10") (pinfunction "IO_L13N_D10_2_R10") (pintype "bidirectional"))
    )
    (net (code "49") (name "/F11") (class "Default")
      (node (ref "PIN40") (pin "49") (pintype "passive"))
      (node (ref "U1") (pin "R11") (pinfunction "IO_L3N_MOSI_CSI_B_MISO0_2_R11") (pintype "bidirectional"))
    )
    (net (code "50") (name "/F12") (class "Default")
      (node (ref "PIN39") (pin "48") (pintype "passive"))
      (node (ref "U1") (pin "G11") (pinfunction "IO_L30P_A21_M1RESET_1_G11") (pintype "bidirectional"))
    )
    (net (code "51") (name "/F13") (class "Default")
      (node (ref "PIN38") (pin "47") (pintype "passive"))
      (node (ref "U1") (pin "J11") (pinfunction "IO_L36P_A9_M1BA0_1_J11") (pintype "bidirectional"))
    )
    (net (code "52") (name "/F14") (class "Default")
      (node (ref "PIN37") (pin "46") (pintype "passive"))
      (node (ref "U1") (pin "K11") (pinfunction "IO_L38N_A4_M1CLKN_1_K11") (pintype "bidirectional"))
    )
    (net (code "53") (name "/F15") (class "Default")
      (node (ref "PIN36") (pin "45") (pintype "passive"))
      (node (ref "U1") (pin "P14") (pinfunction "IO_L74P_AWAKE_1_P14") (pintype "bidirectional"))
    )
    (net (code "54") (name "/F16") (class "Default")
      (node (ref "PIN35") (pin "44") (pintype "passive"))
      (node (ref "U1") (pin "P15") (pinfunction "IO_L74N_DOUT_BUSY_1_P15") (pintype "bidirectional"))
    )
    (net (code "55") (name "/F17") (class "Default")
      (node (ref "PIN34") (pin "43") (pintype "passive"))
      (node (ref "U1") (pin "N14") (pinfunction "IO_L47P_FWE_B_M1DQ0_1_N14") (pintype "bidirectional"))
    )
    (net (code "56") (name "/F18") (class "Default")
      (node (ref "PIN33") (pin "42") (pintype "passive"))
      (node (ref "U1") (pin "N15") (pinfunction "IO_L47N_LDC_M1DQ1_1_N15") (pintype "bidirectional"))
    )
    (net (code "57") (name "/F19") (class "Default")
      (node (ref "PIN32") (pin "41") (pintype "passive"))
      (node (ref "U1") (pin "M13") (pinfunction "IO_L46P_FCS_B_M1DQ2_1_M13") (pintype "bidirectional"))
    )
    (net (code "58") (name "/F20") (class "Default")
      (node (ref "PIN31") (pin "40") (pintype "passive"))
      (node (ref "U1") (pin "M15") (pinfunction "IO_L46N_FOE_B_M1DQ3_1_M15") (pintype "bidirectional"))
    )
    (net (code "59") (name "/F21") (class "Default")
      (node (ref "PIN30") (pin "39") (pintype "passive"))
      (node (ref "U1") (pin "L12") (pinfunction "IO_L40N_GCLK10_M1A6_1_L12") (pintype "bidirectional"))
    )
    (net (code "60") (name "/F22") (class "Default")
      (node (ref "PIN29") (pin "38") (pintype "passive"))
      (node (ref "U1") (pin "L15") (pinfunction "IO_L45N_A0_M1LDQSN_1_L15") (pintype "bidirectional"))
    )
    (net (code "61") (name "/F23") (class "Default")
      (node (ref "PIN28") (pin "37") (pintype "passive"))
      (node (ref "U1") (pin "L14") (pinfunction "IO_L45P_A1_M1LDQS_1_L14") (pintype "bidirectional"))
    )
    (net (code "62") (name "/F24") (class "Default")
      (node (ref "PIN27") (pin "36") (pintype "passive"))
      (node (ref "U1") (pin "K15") (pinfunction "IO_L44N_A2_M1DQ7_1_K15") (pintype "bidirectional"))
    )
    (net (code "63") (name "/F25") (class "Default")
      (node (ref "PIN26") (pin "35") (pintype "passive"))
      (node (ref "U1") (pin "J15") (pinfunction "IO_L43N_GCLK4_M1DQ5_1_J15") (pintype "bidirectional"))
    )
    (net (code "64") (name "/F26") (class "Default")
      (node (ref "PIN25") (pin "34") (pintype "passive"))
      (node (ref "U1") (pin "G15") (pinfunction "IO_L41N_GCLK8_M1CASN_1_G15") (pintype "bidirectional"))
    )
    (net (code "65") (name "/F27") (class "Default")
      (node (ref "PIN24") (pin "33") (pintype "passive"))
      (node (ref "U1") (pin "E15") (pinfunction "IO_L37N_A6_M1A1_1_E15") (pintype "bidirectional"))
    )
    (net (code "66") (name "/F28") (class "Default")
      (node (ref "PIN23") (pin "32") (pintype "passive"))
      (node (ref "U1") (pin "D15") (pinfunction "IO_L35N_A10_M1A2_1_D15") (pintype "bidirectional"))
    )
    (net (code "67") (name "/F29") (class "Default")
      (node (ref "PIN22") (pin "31") (pintype "passive"))
      (node (ref "U1") (pin "K12") (pinfunction "IO_L40P_GCLK11_M1A5_1_K12") (pintype "bidirectional"))
    )
    (net (code "68") (name "/F30") (class "Default")
      (node (ref "PIN21") (pin "30") (pintype "passive"))
      (node (ref "U1") (pin "K13") (pinfunction "IO_L44P_A3_M1DQ6_1_K13") (pintype "bidirectional"))
    )
    (net (code "69") (name "/F31") (class "Default")
      (node (ref "PIN20") (pin "29") (pintype "passive"))
      (node (ref "U1") (pin "J13") (pinfunction "IO_L36N_A8_M1BA1_1_J13") (pintype "bidirectional"))
    )
    (net (code "70") (name "/F32") (class "Default")
      (node (ref "PIN17") (pin "26") (pintype "passive"))
      (node (ref "U1") (pin "H15") (pinfunction "IO_L42N_GCLK6_TRDY1_M1LDM_1_H15") (pintype "bidirectional"))
    )
    (net (code "71") (name "/F33") (class "Default")
      (node (ref "PIN16") (pin "25") (pintype "passive"))
      (node (ref "U1") (pin "C14") (pinfunction "IO_L33P_A15_M1A10_1_C14") (pintype "bidirectional"))
    )
    (net (code "72") (name "/F34") (class "Default")
      (node (ref "PIN15") (pin "24") (pintype "passive"))
      (node (ref "U1") (pin "B14") (pinfunction "IO_L1P_A25_1_B14") (pintype "bidirectional"))
    )
    (net (code "73") (name "/F35") (class "Default")
      (node (ref "PIN14") (pin "23") (pintype "passive"))
      (node (ref "U1") (pin "E14") (pinfunction "IO_L37P_A7_M1A0_1_E14") (pintype "bidirectional"))
    )
    (net (code "74") (name "/F36") (class "Default")
      (node (ref "PIN13") (pin "22") (pintype "passive"))
      (node (ref "U1") (pin "G14") (pinfunction "IO_L41P_GCLK9_IRDY1_M1RASN_1_G14") (pintype "bidirectional"))
    )
    (net (code "75") (name "/F37") (class "Default")
      (node (ref "PIN12") (pin "21") (pintype "passive"))
      (node (ref "U1") (pin "H13") (pinfunction "IO_L42P_GCLK7_M1UDM_1_H13") (pintype "bidirectional"))
    )
    (net (code "76") (name "/F38") (class "Default")
      (node (ref "PIN11") (pin "20") (pintype "passive"))
      (node (ref "U1") (pin "F13") (pinfunction "IO_L39P_M1A3_1_F13") (pintype "bidirectional"))
    )
    (net (code "77") (name "/F39") (class "Default")
      (node (ref "PIN10") (pin "19") (pintype "passive"))
      (node (ref "U1") (pin "G13") (pinfunction "IO_L34N_A12_M1BA2_1_G13") (pintype "bidirectional"))
    )
    (net (code "78") (name "/F40") (class "Default")
      (node (ref "PIN9") (pin "18") (pintype "passive"))
      (node (ref "U1") (pin "F12") (pinfunction "IO_L31N_A18_M1A12_1_F12") (pintype "bidirectional"))
    )
    (net (code "79") (name "/F41") (class "Default")
      (node (ref "PIN8") (pin "17") (pintype "passive"))
      (node (ref "U1") (pin "G12") (pinfunction "IO_L30N_A20_M1A11_1_G12") (pintype "bidirectional"))
    )
    (net (code "80") (name "/F42") (class "Default")
      (node (ref "PIN7") (pin "16") (pintype "passive"))
      (node (ref "U1") (pin "F11") (pinfunction "IO_L31P_A19_M1CKE_1_F11") (pintype "bidirectional"))
    )
    (net (code "81") (name "/F43") (class "Default")
      (node (ref "PIN6") (pin "15") (pintype "passive"))
      (node (ref "U1") (pin "H12") (pinfunction "IO_L34P_A13_M1WE_1_H12") (pintype "bidirectional"))
    )
    (net (code "82") (name "/F44") (class "Default")
      (node (ref "PIN5") (pin "14") (pintype "passive"))
      (node (ref "U1") (pin "B15") (pinfunction "IO_L1N_A24_VREF_1_B15") (pintype "bidirectional"))
    )
    (net (code "83") (name "/FX") (class "Default")
      (node (ref "PIN18") (pin "27") (pintype "passive"))
      (node (ref "U1") (pin "J14") (pinfunction "IO_L43P_GCLK5_M1DQ4_1_J14") (pintype "bidirectional"))
    )
    (net (code "84") (name "/GCLK") (class "Default")
      (node (ref "R8") (pin "2") (pintype "passive"))
      (node (ref "U1") (pin "N7") (pinfunction "IO_L30N_GCLK0_USERCCLK_2_N7") (pintype "bidirectional"))
    )
    (net (code "85") (name "/INIT") (class "Default")
      (node (ref "PIN65") (pin "6") (pintype "passive"))
      (node (ref "R11") (pin "2") (pintype "passive"))
      (node (ref "U7") (pin "8") (pinfunction "OE/~{RESET}_8") (pintype "bidirectional"))
      (node (ref "X2") (pin "10") (pinfunction "10_10") (pintype "passive"))
    )
    (net (code "86") (name "/LED1") (class "Default")
      (node (ref "R13") (pin "2") (pintype "passive"))
      (node (ref "U1") (pin "M6") (pinfunction "IO_L47N_2_M6") (pintype "bidirectional"))
    )
    (net (code "87") (name "/LED2") (class "Default")
      (node (ref "R14") (pin "2") (pintype "passive"))
      (node (ref "U1") (pin "L6") (pinfunction "IO_L62P_D5_2_L6") (pintype "bidirectional"))
    )
    (net (code "88") (name "/LED3") (class "Default")
      (node (ref "R16") (pin "2") (pintype "passive"))
      (node (ref "U1") (pin "L7") (pinfunction "IO_L47P_2_L7") (pintype "bidirectional"))
    )
    (net (code "89") (name "/LED4") (class "Default")
      (node (ref "R17") (pin "2") (pintype "passive"))
      (node (ref "U1") (pin "M8") (pinfunction "IO_L30P_GCLK1_D13_2_M8") (pintype "bidirectional"))
    )
    (net (code "90") (name "/MISO") (class "Default")
      (node (ref "U1") (pin "M5") (pinfunction "IO_L64P_D8_2_M5") (pintype "bidirectional"))
      (node (ref "U3") (pin "7") (pinfunction "SDO_7") (pintype "passive"))
      (node (ref "X1") (pin "7") (pinfunction "DAT0/MISO_7") (pintype "passive"))
    )
    (net (code "91") (name "/MOSI") (class "Default")
      (node (ref "U1") (pin "L8") (pinfunction "IO_L31N_GCLK30_D15_2_L8") (pintype "bidirectional"))
      (node (ref "U3") (pin "13") (pinfunction "SDI_13") (pintype "passive"))
      (node (ref "X1") (pin "3") (pinfunction "CMD/MOSI_3") (pintype "passive"))
    )
    (net (code "92") (name "/P0") (class "Default")
      (node (ref "PIN52") (pin "61") (pintype "passive"))
      (node (ref "U3") (pin "2") (pinfunction "IO0_2") (pintype "passive"))
    )
    (net (code "93") (name "/P1") (class "Default")
      (node (ref "PIN53") (pin "62") (pintype "passive"))
      (node (ref "U3") (pin "3") (pinfunction "IO1_3") (pintype "passive"))
    )
    (net (code "94") (name "/P2") (class "Default")
      (node (ref "PIN54") (pin "63") (pintype "passive"))
      (node (ref "U3") (pin "4") (pinfunction "IO2_4") (pintype "passive"))
    )
    (net (code "95") (name "/P3") (class "Default")
      (node (ref "PIN55") (pin "64") (pintype "passive"))
      (node (ref "U3") (pin "5") (pinfunction "IO3_5") (pintype "passive"))
    )
    (net (code "96") (name "/P4") (class "Default")
      (node (ref "PIN56") (pin "65") (pintype "passive"))
      (node (ref "U3") (pin "8") (pinfunction "IO4_8") (pintype "passive"))
    )
    (net (code "97") (name "/P5") (class "Default")
      (node (ref "PIN57") (pin "66") (pintype "passive"))
      (node (ref "U3") (pin "9") (pinfunction "IO5_9") (pintype "passive"))
    )
    (net (code "98") (name "/P6") (class "Default")
      (node (ref "PIN58") (pin "67") (pintype "passive"))
      (node (ref "U3") (pin "10") (pinfunction "IO6_10") (pintype "passive"))
    )
    (net (code "99") (name "/P7") (class "Default")
      (node (ref "PIN59") (pin "68") (pintype "passive"))
      (node (ref "U3") (pin "11") (pinfunction "IO7_11") (pintype "passive"))
    )
    (net (code "100") (name "/PWRON") (class "Default")
      (node (ref "PIN68") (pin "9") (pintype "passive"))
      (node (ref "U2") (pin "5") (pinfunction "EN1_5") (pintype "passive"))
    )
    (net (code "101") (name "/RAS") (class "Default")
      (node (ref "U1") (pin "K4") (pinfunction "IO_L43P_GCLK23_M3RASN_3_K4") (pintype "bidirectional"))
      (node (ref "U4") (pin "H7") (pinfunction "#RAS_H7") (pintype "passive"))
    )
    (net (code "102") (name "/SCLK") (class "Default")
      (node (ref "U1") (pin "N6") (pinfunction "IO_L48P_D7_2_N6") (pintype "bidirectional"))
      (node (ref "U3") (pin "14") (pinfunction "SCLK_14") (pintype "passive"))
      (node (ref "X1") (pin "5") (pinfunction "CLK_5") (pintype "passive"))
    )
    (net (code "103") (name "/TCK") (class "Default")
      (node (ref "PIN62") (pin "3") (pintype "passive"))
      (node (ref "U1") (pin "A14") (pinfunction "TCK_A14") (pintype "input"))
      (node (ref "U7") (pin "6") (pinfunction "TCK_6") (pintype "input"))
      (node (ref "X2") (pin "4") (pinfunction "4_4") (pintype "passive"))
    )
    (net (code "104") (name "/TDI") (class "Default")
      (node (ref "PIN64") (pin "5") (pintype "passive"))
      (node (ref "U1") (pin "E10") (pinfunction "TDI_E10") (pintype "input"))
      (node (ref "X2") (pin "8") (pinfunction "8_8") (pintype "passive"))
    )
    (net (code "105") (name "/TDO") (class "Default")
      (node (ref "PIN63") (pin "4") (pintype "passive"))
      (node (ref "U7") (pin "17") (pinfunction "TDO_17") (pintype "output"))
      (node (ref "X2") (pin "6") (pinfunction "6_6") (pintype "passive"))
    )
    (net (code "106") (name "/TMS") (class "Default")
      (node (ref "PIN61") (pin "2") (pintype "passive"))
      (node (ref "U1") (pin "E13") (pinfunction "TMS_E13") (pintype "input"))
      (node (ref "U7") (pin "5") (pinfunction "TMS_5") (pintype "input"))
      (node (ref "X2") (pin "2") (pinfunction "2_2") (pintype "passive"))
    )
    (net (code "107") (name "/WE") (class "Default")
      (node (ref "U1") (pin "F5") (pinfunction "IO_L50P_M3WE_3_F5") (pintype "bidirectional"))
      (node (ref "U4") (pin "G7") (pinfunction "#WE_G7") (pintype "passive"))
    )
    (net (code "108") (name "/~IO") (class "Default")
      (node (ref "R1") (pin "2") (pintype "passive"))
      (node (ref "U1") (pin "N5") (pinfunction "IO_L64N_D9_2_N5") (pintype "bidirectional"))
      (node (ref "U3") (pin "16") (pinfunction "~SYNC_16") (pintype "passive"))
    )
    (net (code "109") (name "/~NOCLK") (class "Default")
      (node (ref "R6") (pin "2") (pintype "passive"))
      (node (ref "U1") (pin "P9") (pinfunction "IO_L16P_2_P9") (pintype "bidirectional"))
      (node (ref "U6") (pin "1") (pinfunction "FS/OE_1") (pintype "passive"))
    )
    (net (code "110") (name "/~RESET") (class "Default")
      (node (ref "PIN4") (pin "13") (pintype "passive"))
      (node (ref "R9") (pin "2") (pintype "passive"))
      (node (ref "SW1") (pin "1") (pintype "passive"))
      (node (ref "U1") (pin "R2") (pinfunction "PROGRAM_B_2_R2") (pintype "input"))
      (node (ref "U7") (pin "7") (pinfunction "~{CF}_7") (pintype "open_collector"))
    )
    (net (code "111") (name "/~SD") (class "Default")
      (node (ref "LED6") (pin "1") (pintype "passive"))
      (node (ref "U1") (pin "K8") (pinfunction "IO_L31P_GCLK31_D14_2_K8") (pintype "bidirectional"))
      (node (ref "X1") (pin "2") (pinfunction "DAT3/~SS_2") (pintype "passive"))
    )
    (net (code "112") (name "GND") (class "Default")
      (node (ref "C1") (pin "1") (pintype "passive"))
      (node (ref "C10") (pin "1") (pintype "passive"))
      (node (ref "C11") (pin "1") (pintype "passive"))
      (node (ref "C12") (pin "2") (pintype "passive"))
      (node (ref "C15") (pin "1") (pintype "passive"))
      (node (ref "C16") (pin "2") (pintype "passive"))
      (node (ref "C18") (pin "1") (pintype "passive"))
      (node (ref "C2") (pin "2") (pintype "passive"))
      (node (ref "C20") (pin "2") (pintype "passive"))
      (node (ref "C21") (pin "1") (pintype "passive"))
      (node (ref "C23") (pin "2") (pintype "passive"))
      (node (ref "C24") (pin "2") (pintype "passive"))
      (node (ref "C26") (pin "2") (pintype "passive"))
      (node (ref "C27") (pin "2") (pintype "passive"))
      (node (ref "C29") (pin "1") (pintype "passive"))
      (node (ref "C3") (pin "1") (pintype "passive"))
      (node (ref "C30") (pin "1") (pintype "passive"))
      (node (ref "C31") (pin "2") (pintype "passive"))
      (node (ref "C32") (pin "2") (pintype "passive"))
      (node (ref "C33") (pin "2") (pintype "passive"))
      (node (ref "C37") (pin "2") (pintype "passive"))
      (node (ref "C38") (pin "1") (pintype "passive"))
      (node (ref "C39") (pin "2") (pintype "passive"))
      (node (ref "C4") (pin "2") (pintype "passive"))
      (node (ref "C41") (pin "1") (pintype "passive"))
      (node (ref "C43") (pin "2") (pintype "passive"))
      (node (ref "C44") (pin "1") (pintype "passive"))
      (node (ref "C45") (pin "2") (pintype "passive"))
      (node (ref "C46") (pin "2") (pintype "passive"))
      (node (ref "C48") (pin "1") (pintype "passive"))
      (node (ref "C49") (pin "2") (pintype "passive"))
      (node (ref "C5") (pin "1") (pintype "passive"))
      (node (ref "C50") (pin "1") (pintype "passive"))
      (node (ref "C52") (pin "1") (pintype "passive"))
      (node (ref "C53") (pin "2") (pintype "passive"))
      (node (ref "C54") (pin "1") (pintype "passive"))
      (node (ref "C55") (pin "2") (pintype "passive"))
      (node (ref "C56") (pin "1") (pintype "passive"))
      (node (ref "C57") (pin "1") (pintype "passive"))
      (node (ref "C58") (pin "1") (pintype "passive"))
      (node (ref "C59") (pin "1") (pintype "passive"))
      (node (ref "C6") (pin "1") (pintype "passive"))
      (node (ref "C7") (pin "2") (pintype "passive"))
      (node (ref "C8") (pin "2") (pintype "passive"))
      (node (ref "C9") (pin "1") (pintype "passive"))
      (node (ref "LED1") (pin "1") (pintype "passive"))
      (node (ref "LED2") (pin "1") (pintype "passive"))
      (node (ref "LED3") (pin "1") (pintype "passive"))
      (node (ref "LED4") (pin "1") (pintype "passive"))
      (node (ref "PIN19") (pin "28") (pintype "passive"))
      (node (ref "PIN2") (pin "11") (pintype "passive"))
      (node (ref "PIN60") (pin "1") (pintype "passive"))
      (node (ref "PIN66") (pin "7") (pintype "passive"))
      (node (ref "Q1") (pin "2") (pinfunction "S_2") (pintype "passive"))
      (node (ref "R4") (pin "1") (pintype "passive"))
      (node (ref "R5") (pin "1") (pintype "passive"))
      (node (ref "SW1") (pin "2") (pintype "passive"))
      (node (ref "U1") (pin "A1") (pinfunction "GND_A1") (pintype "power_in"))
      (node (ref "U1") (pin "A15") (pinfunction "GND_A15") (pintype "power_in"))
      (node (ref "U1") (pin "B10") (pinfunction "GND_B10") (pintype "power_in"))
      (node (ref "U1") (pin "B6") (pinfunction "GND_B6") (pintype "power_in"))
      (node (ref "U1") (pin "C13") (pinfunction "GND_C13") (pintype "power_in"))
      (node (ref "U1") (pin "C3") (pinfunction "GND_C3") (pintype "power_in"))
      (node (ref "U1") (pin "E11") (pinfunction "GND_E11") (pintype "power_in"))
      (node (ref "U1") (pin "F14") (pinfunction "GND_F14") (pintype "power_in"))
      (node (ref "U1") (pin "F2") (pinfunction "GND_F2") (pintype "power_in"))
      (node (ref "U1") (pin "F6") (pinfunction "GND_F6") (pintype "power_in"))
      (node (ref "U1") (pin "G7") (pinfunction "GND_G7") (pintype "power_in"))
      (node (ref "U1") (pin "G9") (pinfunction "GND_G9") (pintype "power_in"))
      (node (ref "U1") (pin "H8") (pinfunction "GND_H8") (pintype "power_in"))
      (node (ref "U1") (pin "J7") (pinfunction "GND_J7") (pintype "power_in"))
      (node (ref "U1") (pin "J9") (pinfunction "GND_J9") (pintype "power_in"))
      (node (ref "U1") (pin "K14") (pinfunction "GND_K14") (pintype "power_in"))
      (node (ref "U1") (pin "K2") (pinfunction "GND_K2") (pintype "power_in"))
      (node (ref "U1") (pin "K6") (pinfunction "GND_K6") (pintype "power_in"))
      (node (ref "U1") (pin "L11") (pinfunction "GND_L11") (pintype "power_in"))
      (node (ref "U1") (pin "L13") (pinfunction "SUSPEND_L13") (pintype "input"))
      (node (ref "U1") (pin "N10") (pinfunction "IO_L13P_M1_2_N10") (pintype "bidirectional"))
      (node (ref "U1") (pin "N13") (pinfunction "GND_N13") (pintype "power_in"))
      (node (ref "U1") (pin "N3") (pinfunction "GND_N3") (pintype "power_in"))
      (node (ref "U1") (pin "P10") (pinfunction "GND_P10") (pintype "power_in"))
      (node (ref "U1") (pin "P6") (pinfunction "GND_P6") (pintype "power_in"))
      (node (ref "U1") (pin "R1") (pinfunction "GND_R1") (pintype "power_in"))
      (node (ref "U1") (pin "R15") (pinfunction "GND_R15") (pintype "power_in"))
      (node (ref "U2") (pin "13") (pinfunction "PGND2_13") (pintype "passive"))
      (node (ref "U2") (pin "17") (pinfunction "PAD_17") (pintype "passive"))
      (node (ref "U2") (pin "4") (pinfunction "PGND1_4") (pintype "passive"))
      (node (ref "U2") (pin "8") (pinfunction "GND_8") (pintype "passive"))
      (node (ref "U3") (pin "12") (pinfunction "GND_12") (pintype "passive"))
      (node (ref "U3") (pin "17") (pinfunction "PAD_17") (pintype "passive"))
      (node (ref "U4") (pin "A1") (pinfunction "VSSQ_A1") (pintype "passive"))
      (node (ref "U4") (pin "A3") (pinfunction "VSS_A3") (pintype "passive"))
      (node (ref "U4") (pin "B8") (pinfunction "VSSQ_B8") (pintype "passive"))
      (node (ref "U4") (pin "C2") (pinfunction "VSSQ_C2") (pintype "passive"))
      (node (ref "U4") (pin "D8") (pinfunction "VSSQ_D8") (pintype "passive"))
      (node (ref "U4") (pin "E2") (pinfunction "VSSQ_E2") (pintype "passive"))
      (node (ref "U4") (pin "F2") (pinfunction "VSS_F2") (pintype "passive"))
      (node (ref "U4") (pin "M3") (pinfunction "VSS_M3") (pintype "passive"))
      (node (ref "U5") (pin "3") (pinfunction "GND_3") (pintype "passive"))
      (node (ref "U5") (pin "7") (pinfunction "PAD_7") (pintype "passive"))
      (node (ref "U6") (pin "2") (pinfunction "GND_2") (pintype "passive"))
      (node (ref "U7") (pin "11") (pinfunction "GND_11") (pintype "power_in"))
      (node (ref "U8") (pin "2") (pinfunction "GND_2") (pintype "passive"))
      (node (ref "U8") (pin "5") (pinfunction "EP_5") (pintype "passive"))
      (node (ref "X1") (pin "0") (pinfunction "MNT_0") (pintype "passive"))
      (node (ref "X1") (pin "6") (pinfunction "GND_6") (pintype "passive"))
      (node (ref "X2") (pin "3") (pinfunction "3_3") (pintype "passive"))
      (node (ref "X2") (pin "5") (pinfunction "5_5") (pintype "passive"))
      (node (ref "X2") (pin "7") (pinfunction "7_7") (pintype "passive"))
      (node (ref "X2") (pin "9") (pinfunction "9_9") (pintype "passive"))
    )
    (net (code "113") (name "Net-(LED1-Pad2)") (class "Default")
      (node (ref "LED1") (pin "2") (pintype "passive"))
      (node (ref "R13") (pin "1") (pintype "passive"))
    )
    (net (code "114") (name "Net-(LED2-Pad2)") (class "Default")
      (node (ref "LED2") (pin "2") (pintype "passive"))
      (node (ref "R14") (pin "1") (pintype "passive"))
    )
    (net (code "115") (name "Net-(LED3-Pad2)") (class "Default")
      (node (ref "LED3") (pin "2") (pintype "passive"))
      (node (ref "R16") (pin "1") (pintype "passive"))
    )
    (net (code "116") (name "Net-(LED4-Pad2)") (class "Default")
      (node (ref "LED4") (pin "2") (pintype "passive"))
      (node (ref "R17") (pin "1") (pintype "passive"))
    )
    (net (code "117") (name "Net-(LED5-Pad2)") (class "Default")
      (node (ref "LED5") (pin "2") (pintype "passive"))
      (node (ref "R15") (pin "1") (pintype "passive"))
    )
    (net (code "118") (name "Net-(LED6-Pad2)") (class "Default")
      (node (ref "LED6") (pin "2") (pintype "passive"))
      (node (ref "R12") (pin "2") (pintype "passive"))
    )
    (net (code "119") (name "Net-(Q1-D)") (class "Default")
      (node (ref "LED5") (pin "1") (pintype "passive"))
      (node (ref "Q1") (pin "3") (pinfunction "D_3") (pintype "passive"))
    )
    (net (code "120") (name "Net-(Q1-G)") (class "Default")
      (node (ref "Q1") (pin "1") (pinfunction "G_1") (pintype "passive"))
      (node (ref "R10") (pin "2") (pintype "passive"))
      (node (ref "U1") (pin "R14") (pinfunction "DONE_2_R14") (pintype "bidirectional"))
      (node (ref "U7") (pin "10") (pinfunction "~{CE}_10") (pintype "input"))
    )
    (net (code "121") (name "Net-(U1E-TDO)") (class "Default")
      (node (ref "U1") (pin "D12") (pinfunction "TDO_D12") (pintype "output"))
      (node (ref "U7") (pin "4") (pinfunction "TDI_4") (pintype "input"))
    )
    (net (code "122") (name "Net-(U2-SS1)") (class "Default")
      (node (ref "C29") (pin "2") (pintype "passive"))
      (node (ref "U2") (pin "6") (pinfunction "SS1_6") (pintype "passive"))
    )
    (net (code "123") (name "Net-(U2-SS2)") (class "Default")
      (node (ref "C30") (pin "2") (pintype "passive"))
      (node (ref "U2") (pin "11") (pinfunction "SS2_11") (pintype "passive"))
    )
    (net (code "124") (name "Net-(U2-SW1)") (class "Default")
      (node (ref "C13") (pin "1") (pintype "passive"))
      (node (ref "L1") (pin "2") (pintype "passive"))
      (node (ref "U2") (pin "3") (pinfunction "SW1_3") (pintype "passive"))
    )
    (net (code "125") (name "Net-(U2-SW2)") (class "Default")
      (node (ref "C14") (pin "1") (pintype "passive"))
      (node (ref "L2") (pin "2") (pintype "passive"))
      (node (ref "U2") (pin "14") (pinfunction "SW2_14") (pintype "passive"))
    )
    (net (code "126") (name "Net-(U2-VBST1)") (class "Default")
      (node (ref "C13") (pin "2") (pintype "passive"))
      (node (ref "U2") (pin "2") (pinfunction "VBST1_2") (pintype "passive"))
    )
    (net (code "127") (name "Net-(U2-VBST2)") (class "Default")
      (node (ref "C14") (pin "2") (pintype "passive"))
      (node (ref "U2") (pin "15") (pinfunction "VBST2_15") (pintype "passive"))
    )
    (net (code "128") (name "Net-(U2-VFB1)") (class "Default")
      (node (ref "R2") (pin "1") (pintype "passive"))
      (node (ref "R4") (pin "2") (pintype "passive"))
      (node (ref "U2") (pin "7") (pinfunction "VFB1_7") (pintype "passive"))
    )
    (net (code "129") (name "Net-(U2-VFB2)") (class "Default")
      (node (ref "R3") (pin "1") (pintype "passive"))
      (node (ref "R5") (pin "2") (pintype "passive"))
      (node (ref "U2") (pin "10") (pinfunction "VFB2_10") (pintype "passive"))
    )
    (net (code "130") (name "Net-(U2-VREG5)") (class "Default")
      (node (ref "C37") (pin "1") (pintype "passive"))
      (node (ref "U2") (pin "9") (pinfunction "VREG5_9") (pintype "passive"))
    )
    (net (code "131") (name "Net-(U3-Vref)") (class "Default")
      (node (ref "C8") (pin "1") (pintype "passive"))
      (node (ref "U3") (pin "6") (pinfunction "Vref_6") (pintype "passive"))
    )
    (net (code "132") (name "Net-(U5-NR{slash}FB)") (class "Default")
      (node (ref "C56") (pin "2") (pintype "passive"))
      (node (ref "U5") (pin "2") (pinfunction "NR/FB_2") (pintype "passive"))
    )
    (net (code "133") (name "Net-(U6-CLK)") (class "Default")
      (node (ref "R8") (pin "1") (pintype "passive"))
      (node (ref "U6") (pin "3") (pinfunction "CLK_3") (pintype "passive"))
    )
    (net (code "134") (name "unconnected-(U1A-IO_L1N_VREF_0-PadA2)") (class "Default")
      (node (ref "U1") (pin "A2") (pinfunction "IO_L1N_VREF_0_A2") (pintype "bidirectional+no_connect"))
    )
    (net (code "135") (name "unconnected-(U1A-IO_L1P_HSWAPEN_0-PadB2)") (class "Default")
      (node (ref "U1") (pin "B2") (pinfunction "IO_L1P_HSWAPEN_0_B2") (pintype "bidirectional+no_connect"))
    )
    (net (code "136") (name "unconnected-(U1A-IO_L2N_0-PadA3)") (class "Default")
      (node (ref "U1") (pin "A3") (pinfunction "IO_L2N_0_A3") (pintype "bidirectional+no_connect"))
    )
    (net (code "137") (name "unconnected-(U1A-IO_L2P_0-PadB3)") (class "Default")
      (node (ref "U1") (pin "B3") (pinfunction "IO_L2P_0_B3") (pintype "bidirectional+no_connect"))
    )
    (net (code "138") (name "unconnected-(U1A-IO_L3N_0-PadC5)") (class "Default")
      (node (ref "U1") (pin "C5") (pinfunction "IO_L3N_0_C5") (pintype "bidirectional+no_connect"))
    )
    (net (code "139") (name "unconnected-(U1A-IO_L3P_0-PadD5)") (class "Default")
      (node (ref "U1") (pin "D5") (pinfunction "IO_L3P_0_D5") (pintype "bidirectional+no_connect"))
    )
    (net (code "140") (name "unconnected-(U1A-IO_L4N_0-PadA4)") (class "Default")
      (node (ref "U1") (pin "A4") (pinfunction "IO_L4N_0_A4") (pintype "bidirectional+no_connect"))
    )
    (net (code "141") (name "unconnected-(U1A-IO_L4P_0-PadC4)") (class "Default")
      (node (ref "U1") (pin "C4") (pinfunction "IO_L4P_0_C4") (pintype "bidirectional+no_connect"))
    )
    (net (code "142") (name "unconnected-(U1A-IO_L5N_0-PadD6)") (class "Default")
      (node (ref "U1") (pin "D6") (pinfunction "IO_L5N_0_D6") (pintype "bidirectional+no_connect"))
    )
    (net (code "143") (name "unconnected-(U1A-IO_L5P_0-PadE6)") (class "Default")
      (node (ref "U1") (pin "E6") (pinfunction "IO_L5P_0_E6") (pintype "bidirectional+no_connect"))
    )
    (net (code "144") (name "unconnected-(U1A-IO_L6N_0-PadA5)") (class "Default")
      (node (ref "U1") (pin "A5") (pinfunction "IO_L6N_0_A5") (pintype "bidirectional+no_connect"))
    )
    (net (code "145") (name "unconnected-(U1A-IO_L6P_0-PadB5)") (class "Default")
      (node (ref "U1") (pin "B5") (pinfunction "IO_L6P_0_B5") (pintype "bidirectional+no_connect"))
    )
    (net (code "146") (name "unconnected-(U1A-IO_L7N_0-PadC7)") (class "Default")
      (node (ref "U1") (pin "C7") (pinfunction "IO_L7N_0_C7") (pintype "bidirectional+no_connect"))
    )
    (net (code "147") (name "unconnected-(U1A-IO_L7P_0-PadD7)") (class "Default")
      (node (ref "U1") (pin "D7") (pinfunction "IO_L7P_0_D7") (pintype "bidirectional+no_connect"))
    )
    (net (code "148") (name "unconnected-(U1A-IO_L33N_0-PadA6)") (class "Default")
      (node (ref "U1") (pin "A6") (pinfunction "IO_L33N_0_A6") (pintype "bidirectional+no_connect"))
    )
    (net (code "149") (name "unconnected-(U1A-IO_L33P_0-PadC6)") (class "Default")
      (node (ref "U1") (pin "C6") (pinfunction "IO_L33P_0_C6") (pintype "bidirectional+no_connect"))
    )
    (net (code "150") (name "unconnected-(U1A-IO_L34N_GCLK18_0-PadD8)") (class "Default")
      (node (ref "U1") (pin "D8") (pinfunction "IO_L34N_GCLK18_0_D8") (pintype "bidirectional+no_connect"))
    )
    (net (code "151") (name "unconnected-(U1A-IO_L34P_GCLK19_0-PadE7)") (class "Default")
      (node (ref "U1") (pin "E7") (pinfunction "IO_L34P_GCLK19_0_E7") (pintype "bidirectional+no_connect"))
    )
    (net (code "152") (name "unconnected-(U1A-IO_L35N_GCLK16_0-PadA7)") (class "Default")
      (node (ref "U1") (pin "A7") (pinfunction "IO_L35N_GCLK16_0_A7") (pintype "bidirectional+no_connect"))
    )
    (net (code "153") (name "unconnected-(U1A-IO_L35P_GCLK17_0-PadB7)") (class "Default")
      (node (ref "U1") (pin "B7") (pinfunction "IO_L35P_GCLK17_0_B7") (pintype "bidirectional+no_connect"))
    )
    (net (code "154") (name "unconnected-(U1A-IO_L36N_GCLK14_0-PadA8)") (class "Default")
      (node (ref "U1") (pin "A8") (pinfunction "IO_L36N_GCLK14_0_A8") (pintype "bidirectional+no_connect"))
    )
    (net (code "155") (name "unconnected-(U1A-IO_L36P_GCLK15_0-PadC8)") (class "Default")
      (node (ref "U1") (pin "C8") (pinfunction "IO_L36P_GCLK15_0_C8") (pintype "bidirectional+no_connect"))
    )
    (net (code "156") (name "unconnected-(U1A-IO_L37N_GCLK12_0-PadA9)") (class "Default")
      (node (ref "U1") (pin "A9") (pinfunction "IO_L37N_GCLK12_0_A9") (pintype "bidirectional+no_connect"))
    )
    (net (code "157") (name "unconnected-(U1A-IO_L37P_GCLK13_0-PadB9)") (class "Default")
      (node (ref "U1") (pin "B9") (pinfunction "IO_L37P_GCLK13_0_B9") (pintype "bidirectional+no_connect"))
    )
    (net (code "158") (name "unconnected-(U1A-IO_L38N_VREF_0-PadE8)") (class "Default")
      (node (ref "U1") (pin "E8") (pinfunction "IO_L38N_VREF_0_E8") (pintype "bidirectional+no_connect"))
    )
    (net (code "159") (name "unconnected-(U1A-IO_L38P_0-PadF8)") (class "Default")
      (node (ref "U1") (pin "F8") (pinfunction "IO_L38P_0_F8") (pintype "bidirectional+no_connect"))
    )
    (net (code "160") (name "unconnected-(U1A-IO_L39N_0-PadC9)") (class "Default")
      (node (ref "U1") (pin "C9") (pinfunction "IO_L39N_0_C9") (pintype "bidirectional+no_connect"))
    )
    (net (code "161") (name "unconnected-(U1A-IO_L39P_0-PadD10)") (class "Default")
      (node (ref "U1") (pin "D10") (pinfunction "IO_L39P_0_D10") (pintype "bidirectional+no_connect"))
    )
    (net (code "162") (name "unconnected-(U1A-IO_L40N_0-PadE9)") (class "Default")
      (node (ref "U1") (pin "E9") (pinfunction "IO_L40N_0_E9") (pintype "bidirectional+no_connect"))
    )
    (net (code "163") (name "unconnected-(U1A-IO_L40P_0-PadF10)") (class "Default")
      (node (ref "U1") (pin "F10") (pinfunction "IO_L40P_0_F10") (pintype "bidirectional+no_connect"))
    )
    (net (code "164") (name "unconnected-(U1A-IO_L62N_VREF_0-PadA10)") (class "Default")
      (node (ref "U1") (pin "A10") (pinfunction "IO_L62N_VREF_0_A10") (pintype "bidirectional+no_connect"))
    )
    (net (code "165") (name "unconnected-(U1A-IO_L62P_0-PadC10)") (class "Default")
      (node (ref "U1") (pin "C10") (pinfunction "IO_L62P_0_C10") (pintype "bidirectional+no_connect"))
    )
    (net (code "166") (name "unconnected-(U1A-IO_L63N_SCP6_0-PadA11)") (class "Default")
      (node (ref "U1") (pin "A11") (pinfunction "IO_L63N_SCP6_0_A11") (pintype "bidirectional+no_connect"))
    )
    (net (code "167") (name "unconnected-(U1A-IO_L63P_SCP7_0-PadB11)") (class "Default")
      (node (ref "U1") (pin "B11") (pinfunction "IO_L63P_SCP7_0_B11") (pintype "bidirectional+no_connect"))
    )
    (net (code "168") (name "unconnected-(U1A-IO_L64N_SCP4_0-PadC11)") (class "Default")
      (node (ref "U1") (pin "C11") (pinfunction "IO_L64N_SCP4_0_C11") (pintype "bidirectional+no_connect"))
    )
    (net (code "169") (name "unconnected-(U1A-IO_L64P_SCP5_0-PadD11)") (class "Default")
      (node (ref "U1") (pin "D11") (pinfunction "IO_L64P_SCP5_0_D11") (pintype "bidirectional+no_connect"))
    )
    (net (code "170") (name "unconnected-(U1A-IO_L65N_SCP2_0-PadA13)") (class "Default")
      (node (ref "U1") (pin "A13") (pinfunction "IO_L65N_SCP2_0_A13") (pintype "bidirectional+no_connect"))
    )
    (net (code "171") (name "unconnected-(U1A-IO_L65P_SCP3_0-PadB13)") (class "Default")
      (node (ref "U1") (pin "B13") (pinfunction "IO_L65P_SCP3_0_B13") (pintype "bidirectional+no_connect"))
    )
    (net (code "172") (name "unconnected-(U1A-IO_L66N_SCP0_0-PadA12)") (class "Default")
      (node (ref "U1") (pin "A12") (pinfunction "IO_L66N_SCP0_0_A12") (pintype "bidirectional+no_connect"))
    )
    (net (code "173") (name "unconnected-(U1A-IO_L66P_SCP1_0-PadC12)") (class "Default")
      (node (ref "U1") (pin "C12") (pinfunction "IO_L66P_SCP1_0_C12") (pintype "bidirectional+no_connect"))
    )
    (net (code "174") (name "unconnected-(U1B-IO_L32N_A16_M1A9_1-PadH11)") (class "Default")
      (node (ref "U1") (pin "H11") (pinfunction "IO_L32N_A16_M1A9_1_H11") (pintype "bidirectional+no_connect"))
    )
    (net (code "175") (name "unconnected-(U1B-IO_L32P_A17_M1A8_1-PadH10)") (class "Default")
      (node (ref "U1") (pin "H10") (pinfunction "IO_L32P_A17_M1A8_1_H10") (pintype "bidirectional+no_connect"))
    )
    (net (code "176") (name "unconnected-(U1B-IO_L33N_A14_M1A4_1-PadC15)") (class "Default")
      (node (ref "U1") (pin "C15") (pinfunction "IO_L33N_A14_M1A4_1_C15") (pintype "bidirectional+no_connect"))
    )
    (net (code "177") (name "unconnected-(U1B-IO_L35P_A11_M1A7_1-PadD13)") (class "Default")
      (node (ref "U1") (pin "D13") (pinfunction "IO_L35P_A11_M1A7_1_D13") (pintype "bidirectional+no_connect"))
    )
    (net (code "178") (name "unconnected-(U1B-IO_L38P_A5_M1CLK_1-PadK10)") (class "Default")
      (node (ref "U1") (pin "K10") (pinfunction "IO_L38P_A5_M1CLK_1_K10") (pintype "bidirectional+no_connect"))
    )
    (net (code "179") (name "unconnected-(U1B-IO_L39N_M1ODT_1-PadF15)") (class "Default")
      (node (ref "U1") (pin "F15") (pinfunction "IO_L39N_M1ODT_1_F15") (pintype "bidirectional+no_connect"))
    )
    (net (code "180") (name "unconnected-(U1C-IO_L14N_D12_2-PadM10)") (class "Default")
      (node (ref "U1") (pin "M10") (pinfunction "IO_L14N_D12_2_M10") (pintype "bidirectional+no_connect"))
    )
    (net (code "181") (name "unconnected-(U1C-IO_L14P_D11_2-PadL9)") (class "Default")
      (node (ref "U1") (pin "L9") (pinfunction "IO_L14P_D11_2_L9") (pintype "bidirectional+no_connect"))
    )
    (net (code "182") (name "unconnected-(U1C-IO_L15N_2-PadN9)") (class "Default")
      (node (ref "U1") (pin "N9") (pinfunction "IO_L15N_2_N9") (pintype "bidirectional+no_connect"))
    )
    (net (code "183") (name "unconnected-(U1C-IO_L15P_2-PadM9)") (class "Default")
      (node (ref "U1") (pin "M9") (pinfunction "IO_L15P_2_M9") (pintype "bidirectional+no_connect"))
    )
    (net (code "184") (name "unconnected-(U1C-IO_L29P_GCLK3_2-PadN8)") (class "Default")
      (node (ref "U1") (pin "N8") (pinfunction "IO_L29P_GCLK3_2_N8") (pintype "bidirectional+no_connect"))
    )
    (net (code "185") (name "unconnected-(U1C-IO_L32P_GCLK29_2-PadP7)") (class "Default")
      (node (ref "U1") (pin "P7") (pinfunction "IO_L32P_GCLK29_2_P7") (pintype "bidirectional+no_connect"))
    )
    (net (code "186") (name "unconnected-(U1C-IO_L49P_D3_2-PadP5)") (class "Default")
      (node (ref "U1") (pin "P5") (pinfunction "IO_L49P_D3_2_P5") (pintype "bidirectional+no_connect"))
    )
    (net (code "187") (name "unconnected-(U1C-IO_L62N_D6_2-PadL5)") (class "Default")
      (node (ref "U1") (pin "L5") (pinfunction "IO_L62N_D6_2_L5") (pintype "bidirectional+no_connect"))
    )
    (net (code "188") (name "unconnected-(U1C-IO_L63P_2-PadN4)") (class "Default")
      (node (ref "U1") (pin "N4") (pinfunction "IO_L63P_2_N4") (pintype "bidirectional+no_connect"))
    )
    (net (code "189") (name "unconnected-(U1C-IO_L65N_CSO_B_2-PadR3)") (class "Default")
      (node (ref "U1") (pin "R3") (pinfunction "IO_L65N_CSO_B_2_R3") (pintype "bidirectional+no_connect"))
    )
    (net (code "190") (name "unconnected-(U1C-IO_L65P_INIT_B_2-PadP3)") (class "Default")
      (node (ref "U1") (pin "P3") (pinfunction "IO_L65P_INIT_B_2_P3") (pintype "bidirectional+no_connect"))
    )
    (net (code "191") (name "unconnected-(U1D-IO_L2N_3-PadP1)") (class "Default")
      (node (ref "U1") (pin "P1") (pinfunction "IO_L2N_3_P1") (pintype "bidirectional+no_connect"))
    )
    (net (code "192") (name "unconnected-(U1D-IO_L2P_3-PadP2)") (class "Default")
      (node (ref "U1") (pin "P2") (pinfunction "IO_L2P_3_P2") (pintype "bidirectional+no_connect"))
    )
    (net (code "193") (name "unconnected-(U1D-IO_L39N_M3LDQSN_3-PadL1)") (class "Default")
      (node (ref "U1") (pin "L1") (pinfunction "IO_L39N_M3LDQSN_3_L1") (pintype "bidirectional+no_connect"))
    )
    (net (code "194") (name "unconnected-(U1D-IO_L42P_GCLK25_TRDY2_M3UDM_3-PadH3)") (class "Default")
      (node (ref "U1") (pin "H3") (pinfunction "IO_L42P_GCLK25_TRDY2_M3UDM_3_H3") (pintype "bidirectional+no_connect"))
    )
    (net (code "195") (name "unconnected-(U1D-IO_L45N_M3ODT_3-PadJ4)") (class "Default")
      (node (ref "U1") (pin "J4") (pinfunction "IO_L45N_M3ODT_3_J4") (pintype "bidirectional+no_connect"))
    )
    (net (code "196") (name "unconnected-(U1D-IO_L50N_M3BA2_3-PadF4)") (class "Default")
      (node (ref "U1") (pin "F4") (pinfunction "IO_L50N_M3BA2_3_F4") (pintype "bidirectional+no_connect"))
    )
    (net (code "197") (name "unconnected-(U1D-IO_L54P_M3RESET_3-PadD3)") (class "Default")
      (node (ref "U1") (pin "D3") (pinfunction "IO_L54P_M3RESET_3_D3") (pintype "bidirectional+no_connect"))
    )
    (net (code "198") (name "unconnected-(U1D-IO_L83P_3-PadC2)") (class "Default")
      (node (ref "U1") (pin "C2") (pinfunction "IO_L83P_3_C2") (pintype "bidirectional+no_connect"))
    )
    (net (code "199") (name "unconnected-(U1E-CMPCS_B_2-PadL10)") (class "Default")
      (node (ref "U1") (pin "L10") (pinfunction "CMPCS_B_2_L10") (pintype "input+no_connect"))
    )
    (net (code "200") (name "unconnected-(U4-NC-PadB1)") (class "Default")
      (node (ref "U4") (pin "B1") (pinfunction "NC_B1") (pintype "passive+no_connect"))
    )
    (net (code "201") (name "unconnected-(U4-NC-PadB9)") (class "Default")
      (node (ref "U4") (pin "B9") (pinfunction "NC_B9") (pintype "passive+no_connect"))
    )
    (net (code "202") (name "unconnected-(U4-NC-PadC1)") (class "Default")
      (node (ref "U4") (pin "C1") (pinfunction "NC_C1") (pintype "passive+no_connect"))
    )
    (net (code "203") (name "unconnected-(U4-NC-PadC9)") (class "Default")
      (node (ref "U4") (pin "C9") (pinfunction "NC_C9") (pintype "passive+no_connect"))
    )
    (net (code "204") (name "unconnected-(U4-NC-PadD1)") (class "Default")
      (node (ref "U4") (pin "D1") (pinfunction "NC_D1") (pintype "passive+no_connect"))
    )
    (net (code "205") (name "unconnected-(U4-NC-PadD9)") (class "Default")
      (node (ref "U4") (pin "D9") (pinfunction "NC_D9") (pintype "passive+no_connect"))
    )
    (net (code "206") (name "unconnected-(U4-NC-PadE1)") (class "Default")
      (node (ref "U4") (pin "E1") (pinfunction "NC_E1") (pintype "passive+no_connect"))
    )
    (net (code "207") (name "unconnected-(U4-NC-PadE7)") (class "Default")
      (node (ref "U4") (pin "E7") (pinfunction "NC_E7") (pintype "passive+no_connect"))
    )
    (net (code "208") (name "unconnected-(U4-NC-PadE9)") (class "Default")
      (node (ref "U4") (pin "E9") (pinfunction "NC_E9") (pintype "passive+no_connect"))
    )
    (net (code "209") (name "unconnected-(U4-NC-PadF7)") (class "Default")
      (node (ref "U4") (pin "F7") (pinfunction "NC_F7") (pintype "passive+no_connect"))
    )
    (net (code "210") (name "unconnected-(U4-NC-PadF9)") (class "Default")
      (node (ref "U4") (pin "F9") (pinfunction "NC_F9") (pintype "passive+no_connect"))
    )
    (net (code "211") (name "unconnected-(U5-N{slash}C-Pad5)") (class "Default")
      (node (ref "U5") (pin "5") (pinfunction "N/C_5") (pintype "passive+no_connect"))
    )
    (net (code "212") (name "unconnected-(U7-DNC-Pad2)") (class "Default")
      (node (ref "U7") (pin "2") (pinfunction "DNC_2") (pintype "passive+no_connect"))
    )
    (net (code "213") (name "unconnected-(U7-DNC-Pad9)") (class "Default")
      (node (ref "U7") (pin "9") (pinfunction "DNC_9") (pintype "passive+no_connect"))
    )
    (net (code "214") (name "unconnected-(U7-DNC-Pad12)") (class "Default")
      (node (ref "U7") (pin "12") (pinfunction "DNC_12") (pintype "passive+no_connect"))
    )
    (net (code "215") (name "unconnected-(U7-DNC-Pad14)") (class "Default")
      (node (ref "U7") (pin "14") (pinfunction "DNC_14") (pintype "passive+no_connect"))
    )
    (net (code "216") (name "unconnected-(U7-DNC-Pad15)") (class "Default")
      (node (ref "U7") (pin "15") (pinfunction "DNC_15") (pintype "passive+no_connect"))
    )
    (net (code "217") (name "unconnected-(U7-DNC-Pad16)") (class "Default")
      (node (ref "U7") (pin "16") (pinfunction "DNC_16") (pintype "passive+no_connect"))
    )
    (net (code "218") (name "unconnected-(U7-~{CEO}-Pad13)") (class "Default")
      (node (ref "U7") (pin "13") (pinfunction "~{CEO}_13") (pintype "output+no_connect"))
    )
    (net (code "219") (name "unconnected-(X1-DAT1-Pad8)") (class "Default")
      (node (ref "X1") (pin "8") (pinfunction "DAT1_8") (pintype "passive+no_connect"))
    )
    (net (code "220") (name "unconnected-(X1-DAT2-Pad1)") (class "Default")
      (node (ref "X1") (pin "1") (pinfunction "DAT2_1") (pintype "passive+no_connect"))
    )
  )
)
